# drivers_lvds.net
KiCad netlist of a schematic drawn in Altium Designer
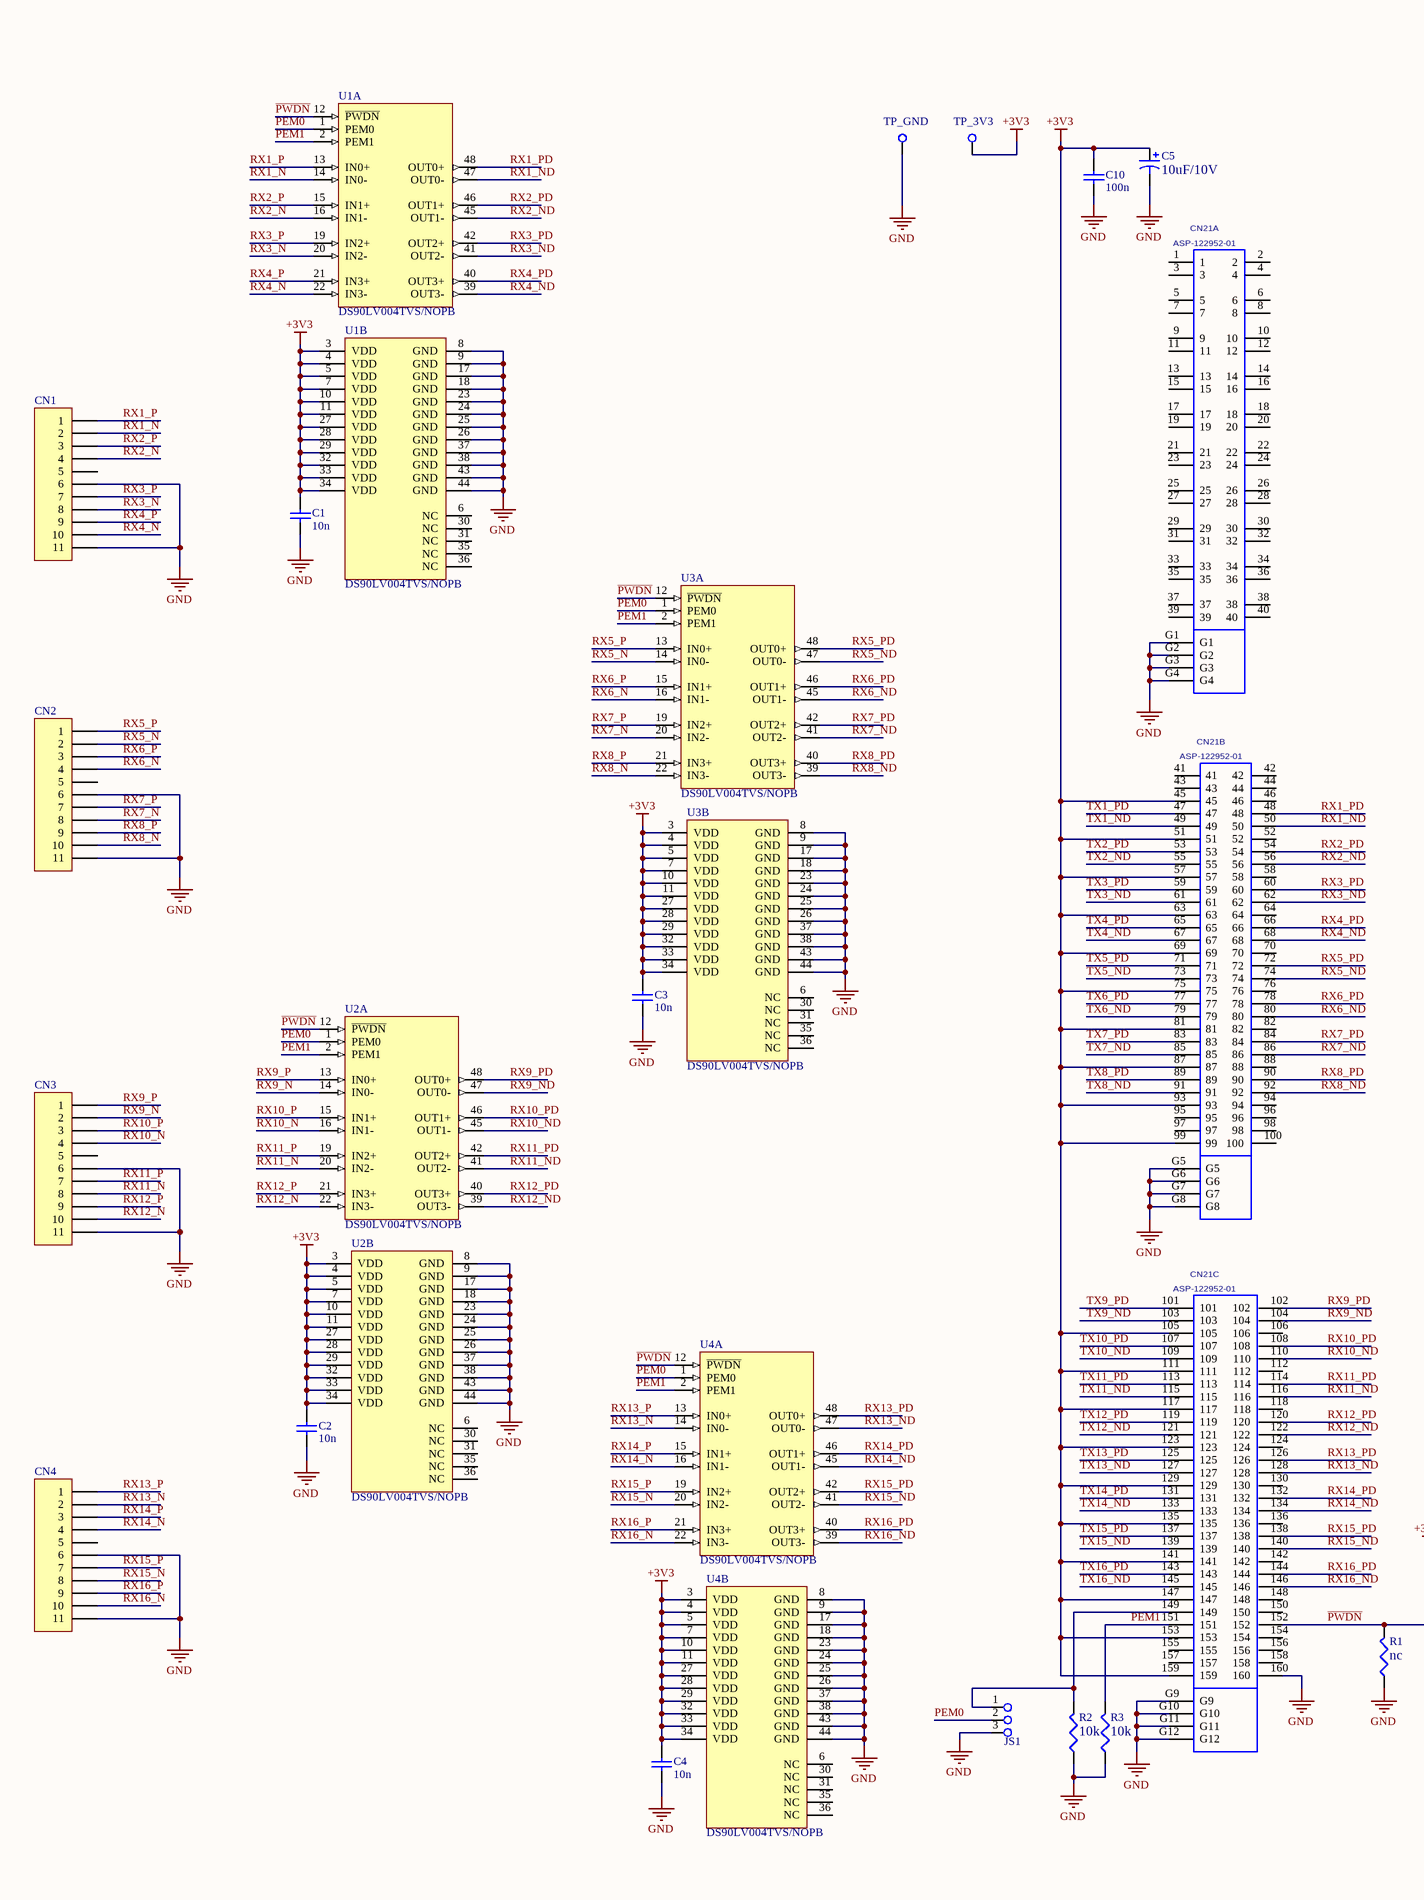
[diagram p0: drivers_lvds.SchDoc, left]
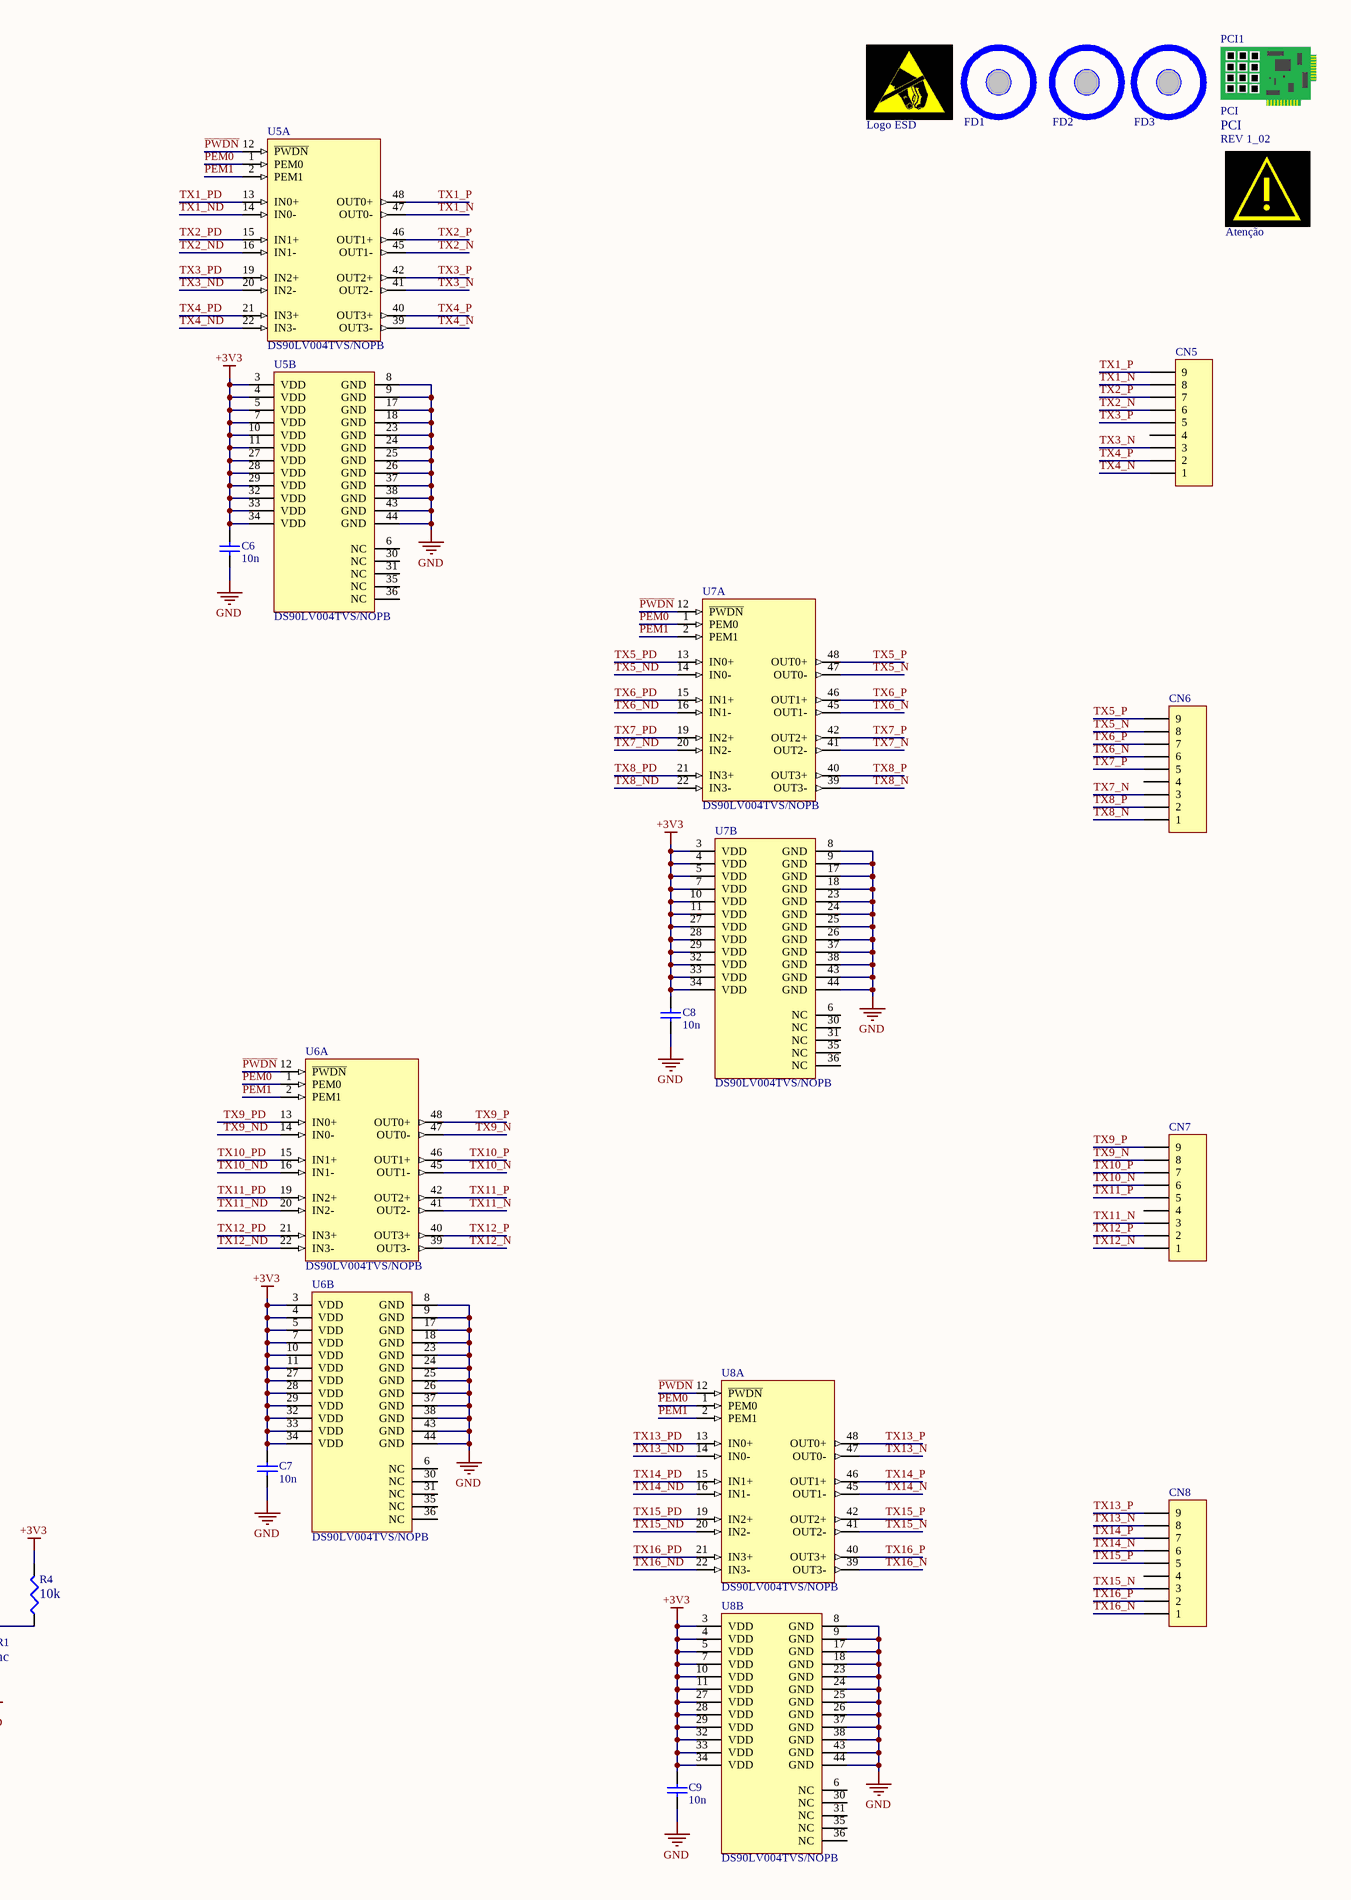
[diagram p1: drivers_lvds.SchDoc, right]

(export (version "E")
  (design (tool "Eeschema 10.0.6"))
  (components
    (comp (ref "AT3")
      (value "##nl")
      (footprint "LEIA_DOCUMENTACAO")
      (description "ATENCAO")
      (fields (field (name "VALOR") "Atenção"))
      (libsource (lib "SIMBOLOS") (part "ATENCAO"))
    )
    (comp (ref "C1")
      (value "Capacitor Cerâmico SMD")
      (footprint "0603 - CAP - montagem na maquina")
      (fields (field (name "VALOR") "10n"))
      (libsource (lib "Miscellaneous Devices") (part "Capacitor Cerâmico SMD"))
    )
    (comp (ref "C2")
      (value "Capacitor Cerâmico SMD")
      (footprint "0603 - CAP - montagem na maquina")
      (fields (field (name "VALOR") "10n"))
      (libsource (lib "Miscellaneous Devices") (part "Capacitor Cerâmico SMD"))
    )
    (comp (ref "C3")
      (value "Capacitor Cerâmico SMD")
      (footprint "0603 - CAP - montagem na maquina")
      (fields (field (name "VALOR") "10n"))
      (libsource (lib "Miscellaneous Devices") (part "Capacitor Cerâmico SMD"))
    )
    (comp (ref "C4")
      (value "Capacitor Cerâmico SMD")
      (footprint "0603 - CAP - montagem na maquina")
      (fields (field (name "VALOR") "10n"))
      (libsource (lib "Miscellaneous Devices") (part "Capacitor Cerâmico SMD"))
    )
    (comp (ref "C5")
      (value "Capacitor de tântalo")
      (footprint "CASE-B")
      (fields (field (name "VALOR") "10uF/10V"))
      (libsource (lib "Miscellaneous Devices") (part "Capacitor de tântalo"))
    )
    (comp (ref "C6")
      (value "Capacitor Cerâmico SMD")
      (footprint "0603 - CAP - montagem na maquina")
      (fields (field (name "VALOR") "10n"))
      (libsource (lib "Miscellaneous Devices") (part "Capacitor Cerâmico SMD"))
    )
    (comp (ref "C7")
      (value "Capacitor Cerâmico SMD")
      (footprint "0603 - CAP - montagem na maquina")
      (fields (field (name "VALOR") "10n"))
      (libsource (lib "Miscellaneous Devices") (part "Capacitor Cerâmico SMD"))
    )
    (comp (ref "C8")
      (value "Capacitor Cerâmico SMD")
      (footprint "0603 - CAP - montagem na maquina")
      (fields (field (name "VALOR") "10n"))
      (libsource (lib "Miscellaneous Devices") (part "Capacitor Cerâmico SMD"))
    )
    (comp (ref "C9")
      (value "Capacitor Cerâmico SMD")
      (footprint "0603 - CAP - montagem na maquina")
      (fields (field (name "VALOR") "10n"))
      (libsource (lib "Miscellaneous Devices") (part "Capacitor Cerâmico SMD"))
    )
    (comp (ref "C10")
      (value "Capacitor Cerâmico SMD")
      (footprint "0603 - CAP - montagem na maquina")
      (fields (field (name "VALOR") "100n"))
      (libsource (lib "Miscellaneous Devices") (part "Capacitor Cerâmico SMD"))
    )
    (comp (ref "CN1")
      (value "MHDR1X11")
      (footprint "MHDR1X11_Axonn")
      (description "Header, 11-Pin")
      (fields (field (name "PUBLISHER") "Altium Limited"))
      (libsource (lib "Miscellaneous Connectors") (part "MHDR1X11"))
    )
    (comp (ref "CN2")
      (value "MHDR1X11")
      (footprint "MHDR1X11_Axonn")
      (description "Header, 11-Pin")
      (fields (field (name "PUBLISHER") "Altium Limited"))
      (libsource (lib "Miscellaneous Connectors") (part "MHDR1X11"))
    )
    (comp (ref "CN3")
      (value "MHDR1X11")
      (footprint "MHDR1X11_Axonn")
      (description "Header, 11-Pin")
      (fields (field (name "PUBLISHER") "Altium Limited"))
      (libsource (lib "Miscellaneous Connectors") (part "MHDR1X11"))
    )
    (comp (ref "CN4")
      (value "MHDR1X11")
      (footprint "MHDR1X11_Axonn")
      (description "Header, 11-Pin")
      (fields (field (name "PUBLISHER") "Altium Limited"))
      (libsource (lib "Miscellaneous Connectors") (part "MHDR1X11"))
    )
    (comp (ref "CN5")
      (value "MHDR1X9")
      (footprint "MHDR1X9_Axonn")
      (description "Header, 9-Pin")
      (fields (field (name "PUBLISHER") "Altium Limited"))
      (libsource (lib "Miscellaneous Connectors") (part "MHDR1X9"))
    )
    (comp (ref "CN6")
      (value "MHDR1X9")
      (footprint "MHDR1X9_Axonn")
      (description "Header, 9-Pin")
      (fields (field (name "PUBLISHER") "Altium Limited"))
      (libsource (lib "Miscellaneous Connectors") (part "MHDR1X9"))
    )
    (comp (ref "CN7")
      (value "MHDR1X9")
      (footprint "MHDR1X9_Axonn")
      (description "Header, 9-Pin")
      (fields (field (name "PUBLISHER") "Altium Limited"))
      (libsource (lib "Miscellaneous Connectors") (part "MHDR1X9"))
    )
    (comp (ref "CN8")
      (value "MHDR1X9")
      (footprint "MHDR1X9_Axonn")
      (description "Header, 9-Pin")
      (fields (field (name "PUBLISHER") "Altium Limited"))
      (libsource (lib "Miscellaneous Connectors") (part "MHDR1X9"))
    )
    (comp (ref "CN21")
      (value "ASP-122952-01")
      (footprint "ASP-122952-01")
      (description "0.5MM PITCH DOUBLE ROW HS TERMINAL ASSEMBLY")
      (fields (field (name "MANUFACTURER") "SAMTEC") (field (name "CREATED") "May 29, 2015 - Wendy Xin"))
      (libsource (lib "ASP-122952-01") (part "ASP-122952-01"))
    )
    (comp (ref "ESD2")
      (value "##nl")
      (footprint "ESTATICA")
      (description "ESD")
      (fields (field (name "VALOR") "Logo ESD"))
      (libsource (lib "SIMBOLOS") (part "ESD"))
    )
    (comp (ref "FD1")
      (value "##nl")
      (footprint "FIDUCIAL")
      (description "Fiducial")
      (libsource (lib "PERIFERICOS") (part "Fiducial"))
    )
    (comp (ref "FD2")
      (value "##nl")
      (footprint "FIDUCIAL")
      (description "Fiducial")
      (libsource (lib "PERIFERICOS") (part "Fiducial"))
    )
    (comp (ref "FD3")
      (value "##nl")
      (footprint "FIDUCIAL")
      (description "Fiducial")
      (libsource (lib "PERIFERICOS") (part "Fiducial"))
    )
    (comp (ref "JS1")
      (value "##Obs")
      (footprint "Jumper de solda 3 vias")
      (description "JUMPER DE SOLDA 3 VIAS")
      (libsource (lib "Miscellaneous Devices") (part "JUMPER SOLDA 3 VIAS"))
    )
    (comp (ref "PCI1")
      (value "PCI")
      (fields (field (name "VALOR") "PCI") (field (name "REV") "REV 1_02"))
      (libsource (lib "PCI") (part "PCI"))
    )
    (comp (ref "R1")
      (value "Res3")
      (footprint "0603 - MONTAGEM MÁQUINA")
      (description "Resistor")
      (fields (field (name "VALOR") "nc"))
      (libsource (lib "Miscellaneous Devices") (part "Res3"))
    )
    (comp (ref "R2")
      (value "Res3")
      (footprint "0603 - MONTAGEM MÁQUINA")
      (description "Resistor")
      (fields (field (name "VALOR") "10k"))
      (libsource (lib "Miscellaneous Devices") (part "Res3"))
    )
    (comp (ref "R3")
      (value "Res3")
      (footprint "0603 - MONTAGEM MÁQUINA")
      (description "Resistor")
      (fields (field (name "VALOR") "10k"))
      (libsource (lib "Miscellaneous Devices") (part "Res3"))
    )
    (comp (ref "R4")
      (value "Res3")
      (footprint "0603 - MONTAGEM MÁQUINA")
      (description "Resistor")
      (fields (field (name "VALOR") "10k"))
      (libsource (lib "Miscellaneous Devices") (part "Res3"))
    )
    (comp (ref "TP_3V3")
      (value "Comment")
      (footprint "Testpoint")
      (description "Testpoint")
      (libsource (lib "Miscellaneous Devices") (part "TESTPOINT"))
    )
    (comp (ref "TP_GND")
      (value "Comment")
      (footprint "Testpoint")
      (description "Testpoint")
      (libsource (lib "Miscellaneous Devices") (part "TESTPOINT"))
    )
    (comp (ref "U1")
      (value "DS90LV004TVS/NOPB")
      (footprint "VBC48A_N")
      (description "4-Channel LVDS Buffer/Repeaters with Pre-Emphasis, 48-pin TQFP, Pb-Free")
      (fields
        (field (name "MANUFACTURER") "National Semiconductor")
        (field (name "PUBLISHER") "Altium Limited")
      )
      (libsource (lib "NSC Interface") (part "DS90LV004TVS/NOPB"))
    )
    (comp (ref "U2")
      (value "DS90LV004TVS/NOPB")
      (footprint "VBC48A_N")
      (description "4-Channel LVDS Buffer/Repeaters with Pre-Emphasis, 48-pin TQFP, Pb-Free")
      (fields
        (field (name "MANUFACTURER") "National Semiconductor")
        (field (name "PUBLISHER") "Altium Limited")
      )
      (libsource (lib "NSC Interface") (part "DS90LV004TVS/NOPB"))
    )
    (comp (ref "U3")
      (value "DS90LV004TVS/NOPB")
      (footprint "VBC48A_N")
      (description "4-Channel LVDS Buffer/Repeaters with Pre-Emphasis, 48-pin TQFP, Pb-Free")
      (fields
        (field (name "MANUFACTURER") "National Semiconductor")
        (field (name "PUBLISHER") "Altium Limited")
      )
      (libsource (lib "NSC Interface") (part "DS90LV004TVS/NOPB"))
    )
    (comp (ref "U4")
      (value "DS90LV004TVS/NOPB")
      (footprint "VBC48A_N")
      (description "4-Channel LVDS Buffer/Repeaters with Pre-Emphasis, 48-pin TQFP, Pb-Free")
      (fields
        (field (name "MANUFACTURER") "National Semiconductor")
        (field (name "PUBLISHER") "Altium Limited")
      )
      (libsource (lib "NSC Interface") (part "DS90LV004TVS/NOPB"))
    )
    (comp (ref "U5")
      (value "DS90LV004TVS/NOPB")
      (footprint "VBC48A_N")
      (description "4-Channel LVDS Buffer/Repeaters with Pre-Emphasis, 48-pin TQFP, Pb-Free")
      (fields
        (field (name "MANUFACTURER") "National Semiconductor")
        (field (name "PUBLISHER") "Altium Limited")
      )
      (libsource (lib "NSC Interface") (part "DS90LV004TVS/NOPB"))
    )
    (comp (ref "U6")
      (value "DS90LV004TVS/NOPB")
      (footprint "VBC48A_N")
      (description "4-Channel LVDS Buffer/Repeaters with Pre-Emphasis, 48-pin TQFP, Pb-Free")
      (fields
        (field (name "MANUFACTURER") "National Semiconductor")
        (field (name "PUBLISHER") "Altium Limited")
      )
      (libsource (lib "NSC Interface") (part "DS90LV004TVS/NOPB"))
    )
    (comp (ref "U7")
      (value "DS90LV004TVS/NOPB")
      (footprint "VBC48A_N")
      (description "4-Channel LVDS Buffer/Repeaters with Pre-Emphasis, 48-pin TQFP, Pb-Free")
      (fields
        (field (name "MANUFACTURER") "National Semiconductor")
        (field (name "PUBLISHER") "Altium Limited")
      )
      (libsource (lib "NSC Interface") (part "DS90LV004TVS/NOPB"))
    )
    (comp (ref "U8")
      (value "DS90LV004TVS/NOPB")
      (footprint "VBC48A_N")
      (description "4-Channel LVDS Buffer/Repeaters with Pre-Emphasis, 48-pin TQFP, Pb-Free")
      (fields
        (field (name "MANUFACTURER") "National Semiconductor")
        (field (name "PUBLISHER") "Altium Limited")
      )
      (libsource (lib "NSC Interface") (part "DS90LV004TVS/NOPB"))
    )
  )
  (nets
    (net (code "1") (name "+3V3") (class "Default")
      (node (ref "C1") (pin "2") (pinfunction "2_2") (pintype "passive"))
      (node (ref "C10") (pin "2") (pinfunction "2_2") (pintype "passive"))
      (node (ref "C2") (pin "2") (pinfunction "2_2") (pintype "passive"))
      (node (ref "C3") (pin "2") (pinfunction "2_2") (pintype "passive"))
      (node (ref "C4") (pin "2") (pinfunction "2_2") (pintype "passive"))
      (node (ref "C5") (pin "1") (pinfunction "1_1") (pintype "passive"))
      (node (ref "C6") (pin "2") (pinfunction "2_2") (pintype "passive"))
      (node (ref "C7") (pin "2") (pinfunction "2_2") (pintype "passive"))
      (node (ref "C8") (pin "2") (pinfunction "2_2") (pintype "passive"))
      (node (ref "C9") (pin "2") (pinfunction "2_2") (pintype "passive"))
      (node (ref "CN21") (pin "105") (pinfunction "105_105") (pintype "passive"))
      (node (ref "CN21") (pin "111") (pinfunction "111_111") (pintype "passive"))
      (node (ref "CN21") (pin "117") (pinfunction "117_117") (pintype "passive"))
      (node (ref "CN21") (pin "123") (pinfunction "123_123") (pintype "passive"))
      (node (ref "CN21") (pin "129") (pinfunction "129_129") (pintype "passive"))
      (node (ref "CN21") (pin "135") (pinfunction "135_135") (pintype "passive"))
      (node (ref "CN21") (pin "141") (pinfunction "141_141") (pintype "passive"))
      (node (ref "CN21") (pin "147") (pinfunction "147_147") (pintype "passive"))
      (node (ref "CN21") (pin "153") (pinfunction "153_153") (pintype "passive"))
      (node (ref "CN21") (pin "159") (pinfunction "159_159") (pintype "passive"))
      (node (ref "CN21") (pin "45") (pinfunction "45_45") (pintype "passive"))
      (node (ref "CN21") (pin "51") (pinfunction "51_51") (pintype "passive"))
      (node (ref "CN21") (pin "57") (pinfunction "57_57") (pintype "passive"))
      (node (ref "CN21") (pin "63") (pinfunction "63_63") (pintype "passive"))
      (node (ref "CN21") (pin "69") (pinfunction "69_69") (pintype "passive"))
      (node (ref "CN21") (pin "75") (pinfunction "75_75") (pintype "passive"))
      (node (ref "CN21") (pin "81") (pinfunction "81_81") (pintype "passive"))
      (node (ref "CN21") (pin "87") (pinfunction "87_87") (pintype "passive"))
      (node (ref "CN21") (pin "93") (pinfunction "93_93") (pintype "passive"))
      (node (ref "CN21") (pin "99") (pinfunction "99_99") (pintype "passive"))
      (node (ref "R4") (pin "2") (pinfunction "2_2") (pintype "passive"))
      (node (ref "TP_3V3") (pin "1") (pinfunction "1_1") (pintype "passive"))
      (node (ref "U1") (pin "10") (pinfunction "VDD_10") (pintype "power_in"))
      (node (ref "U1") (pin "11") (pinfunction "VDD_11") (pintype "power_in"))
      (node (ref "U1") (pin "27") (pinfunction "VDD_27") (pintype "power_in"))
      (node (ref "U1") (pin "28") (pinfunction "VDD_28") (pintype "power_in"))
      (node (ref "U1") (pin "29") (pinfunction "VDD_29") (pintype "power_in"))
      (node (ref "U1") (pin "3") (pinfunction "VDD_3") (pintype "power_in"))
      (node (ref "U1") (pin "32") (pinfunction "VDD_32") (pintype "power_in"))
      (node (ref "U1") (pin "33") (pinfunction "VDD_33") (pintype "power_in"))
      (node (ref "U1") (pin "34") (pinfunction "VDD_34") (pintype "power_in"))
      (node (ref "U1") (pin "4") (pinfunction "VDD_4") (pintype "power_in"))
      (node (ref "U1") (pin "5") (pinfunction "VDD_5") (pintype "power_in"))
      (node (ref "U1") (pin "7") (pinfunction "VDD_7") (pintype "power_in"))
      (node (ref "U2") (pin "10") (pinfunction "VDD_10") (pintype "power_in"))
      (node (ref "U2") (pin "11") (pinfunction "VDD_11") (pintype "power_in"))
      (node (ref "U2") (pin "27") (pinfunction "VDD_27") (pintype "power_in"))
      (node (ref "U2") (pin "28") (pinfunction "VDD_28") (pintype "power_in"))
      (node (ref "U2") (pin "29") (pinfunction "VDD_29") (pintype "power_in"))
      (node (ref "U2") (pin "3") (pinfunction "VDD_3") (pintype "power_in"))
      (node (ref "U2") (pin "32") (pinfunction "VDD_32") (pintype "power_in"))
      (node (ref "U2") (pin "33") (pinfunction "VDD_33") (pintype "power_in"))
      (node (ref "U2") (pin "34") (pinfunction "VDD_34") (pintype "power_in"))
      (node (ref "U2") (pin "4") (pinfunction "VDD_4") (pintype "power_in"))
      (node (ref "U2") (pin "5") (pinfunction "VDD_5") (pintype "power_in"))
      (node (ref "U2") (pin "7") (pinfunction "VDD_7") (pintype "power_in"))
      (node (ref "U3") (pin "10") (pinfunction "VDD_10") (pintype "power_in"))
      (node (ref "U3") (pin "11") (pinfunction "VDD_11") (pintype "power_in"))
      (node (ref "U3") (pin "27") (pinfunction "VDD_27") (pintype "power_in"))
      (node (ref "U3") (pin "28") (pinfunction "VDD_28") (pintype "power_in"))
      (node (ref "U3") (pin "29") (pinfunction "VDD_29") (pintype "power_in"))
      (node (ref "U3") (pin "3") (pinfunction "VDD_3") (pintype "power_in"))
      (node (ref "U3") (pin "32") (pinfunction "VDD_32") (pintype "power_in"))
      (node (ref "U3") (pin "33") (pinfunction "VDD_33") (pintype "power_in"))
      (node (ref "U3") (pin "34") (pinfunction "VDD_34") (pintype "power_in"))
      (node (ref "U3") (pin "4") (pinfunction "VDD_4") (pintype "power_in"))
      (node (ref "U3") (pin "5") (pinfunction "VDD_5") (pintype "power_in"))
      (node (ref "U3") (pin "7") (pinfunction "VDD_7") (pintype "power_in"))
      (node (ref "U4") (pin "10") (pinfunction "VDD_10") (pintype "power_in"))
      (node (ref "U4") (pin "11") (pinfunction "VDD_11") (pintype "power_in"))
      (node (ref "U4") (pin "27") (pinfunction "VDD_27") (pintype "power_in"))
      (node (ref "U4") (pin "28") (pinfunction "VDD_28") (pintype "power_in"))
      (node (ref "U4") (pin "29") (pinfunction "VDD_29") (pintype "power_in"))
      (node (ref "U4") (pin "3") (pinfunction "VDD_3") (pintype "power_in"))
      (node (ref "U4") (pin "32") (pinfunction "VDD_32") (pintype "power_in"))
      (node (ref "U4") (pin "33") (pinfunction "VDD_33") (pintype "power_in"))
      (node (ref "U4") (pin "34") (pinfunction "VDD_34") (pintype "power_in"))
      (node (ref "U4") (pin "4") (pinfunction "VDD_4") (pintype "power_in"))
      (node (ref "U4") (pin "5") (pinfunction "VDD_5") (pintype "power_in"))
      (node (ref "U4") (pin "7") (pinfunction "VDD_7") (pintype "power_in"))
      (node (ref "U5") (pin "10") (pinfunction "VDD_10") (pintype "power_in"))
      (node (ref "U5") (pin "11") (pinfunction "VDD_11") (pintype "power_in"))
      (node (ref "U5") (pin "27") (pinfunction "VDD_27") (pintype "power_in"))
      (node (ref "U5") (pin "28") (pinfunction "VDD_28") (pintype "power_in"))
      (node (ref "U5") (pin "29") (pinfunction "VDD_29") (pintype "power_in"))
      (node (ref "U5") (pin "3") (pinfunction "VDD_3") (pintype "power_in"))
      (node (ref "U5") (pin "32") (pinfunction "VDD_32") (pintype "power_in"))
      (node (ref "U5") (pin "33") (pinfunction "VDD_33") (pintype "power_in"))
      (node (ref "U5") (pin "34") (pinfunction "VDD_34") (pintype "power_in"))
      (node (ref "U5") (pin "4") (pinfunction "VDD_4") (pintype "power_in"))
      (node (ref "U5") (pin "5") (pinfunction "VDD_5") (pintype "power_in"))
      (node (ref "U5") (pin "7") (pinfunction "VDD_7") (pintype "power_in"))
      (node (ref "U6") (pin "10") (pinfunction "VDD_10") (pintype "power_in"))
      (node (ref "U6") (pin "11") (pinfunction "VDD_11") (pintype "power_in"))
      (node (ref "U6") (pin "27") (pinfunction "VDD_27") (pintype "power_in"))
      (node (ref "U6") (pin "28") (pinfunction "VDD_28") (pintype "power_in"))
      (node (ref "U6") (pin "29") (pinfunction "VDD_29") (pintype "power_in"))
      (node (ref "U6") (pin "3") (pinfunction "VDD_3") (pintype "power_in"))
      (node (ref "U6") (pin "32") (pinfunction "VDD_32") (pintype "power_in"))
      (node (ref "U6") (pin "33") (pinfunction "VDD_33") (pintype "power_in"))
      (node (ref "U6") (pin "34") (pinfunction "VDD_34") (pintype "power_in"))
      (node (ref "U6") (pin "4") (pinfunction "VDD_4") (pintype "power_in"))
      (node (ref "U6") (pin "5") (pinfunction "VDD_5") (pintype "power_in"))
      (node (ref "U6") (pin "7") (pinfunction "VDD_7") (pintype "power_in"))
      (node (ref "U7") (pin "10") (pinfunction "VDD_10") (pintype "power_in"))
      (node (ref "U7") (pin "11") (pinfunction "VDD_11") (pintype "power_in"))
      (node (ref "U7") (pin "27") (pinfunction "VDD_27") (pintype "power_in"))
      (node (ref "U7") (pin "28") (pinfunction "VDD_28") (pintype "power_in"))
      (node (ref "U7") (pin "29") (pinfunction "VDD_29") (pintype "power_in"))
      (node (ref "U7") (pin "3") (pinfunction "VDD_3") (pintype "power_in"))
      (node (ref "U7") (pin "32") (pinfunction "VDD_32") (pintype "power_in"))
      (node (ref "U7") (pin "33") (pinfunction "VDD_33") (pintype "power_in"))
      (node (ref "U7") (pin "34") (pinfunction "VDD_34") (pintype "power_in"))
      (node (ref "U7") (pin "4") (pinfunction "VDD_4") (pintype "power_in"))
      (node (ref "U7") (pin "5") (pinfunction "VDD_5") (pintype "power_in"))
      (node (ref "U7") (pin "7") (pinfunction "VDD_7") (pintype "power_in"))
      (node (ref "U8") (pin "10") (pinfunction "VDD_10") (pintype "power_in"))
      (node (ref "U8") (pin "11") (pinfunction "VDD_11") (pintype "power_in"))
      (node (ref "U8") (pin "27") (pinfunction "VDD_27") (pintype "power_in"))
      (node (ref "U8") (pin "28") (pinfunction "VDD_28") (pintype "power_in"))
      (node (ref "U8") (pin "29") (pinfunction "VDD_29") (pintype "power_in"))
      (node (ref "U8") (pin "3") (pinfunction "VDD_3") (pintype "power_in"))
      (node (ref "U8") (pin "32") (pinfunction "VDD_32") (pintype "power_in"))
      (node (ref "U8") (pin "33") (pinfunction "VDD_33") (pintype "power_in"))
      (node (ref "U8") (pin "34") (pinfunction "VDD_34") (pintype "power_in"))
      (node (ref "U8") (pin "4") (pinfunction "VDD_4") (pintype "power_in"))
      (node (ref "U8") (pin "5") (pinfunction "VDD_5") (pintype "power_in"))
      (node (ref "U8") (pin "7") (pinfunction "VDD_7") (pintype "power_in"))
    )
    (net (code "2") (name "/PEM0") (class "Default")
      (node (ref "JS1") (pin "2") (pinfunction "3_2") (pintype "passive"))
      (node (ref "U1") (pin "1") (pinfunction "PEM0_1") (pintype "input"))
      (node (ref "U2") (pin "1") (pinfunction "PEM0_1") (pintype "input"))
      (node (ref "U3") (pin "1") (pinfunction "PEM0_1") (pintype "input"))
      (node (ref "U4") (pin "1") (pinfunction "PEM0_1") (pintype "input"))
      (node (ref "U5") (pin "1") (pinfunction "PEM0_1") (pintype "input"))
      (node (ref "U6") (pin "1") (pinfunction "PEM0_1") (pintype "input"))
      (node (ref "U7") (pin "1") (pinfunction "PEM0_1") (pintype "input"))
      (node (ref "U8") (pin "1") (pinfunction "PEM0_1") (pintype "input"))
    )
    (net (code "3") (name "/PEM1") (class "Default")
      (node (ref "CN21") (pin "151") (pinfunction "151_151") (pintype "passive"))
      (node (ref "R3") (pin "2") (pinfunction "2_2") (pintype "passive"))
      (node (ref "U1") (pin "2") (pinfunction "PEM1_2") (pintype "input"))
      (node (ref "U2") (pin "2") (pinfunction "PEM1_2") (pintype "input"))
      (node (ref "U3") (pin "2") (pinfunction "PEM1_2") (pintype "input"))
      (node (ref "U4") (pin "2") (pinfunction "PEM1_2") (pintype "input"))
      (node (ref "U5") (pin "2") (pinfunction "PEM1_2") (pintype "input"))
      (node (ref "U6") (pin "2") (pinfunction "PEM1_2") (pintype "input"))
      (node (ref "U7") (pin "2") (pinfunction "PEM1_2") (pintype "input"))
      (node (ref "U8") (pin "2") (pinfunction "PEM1_2") (pintype "input"))
    )
    (net (code "4") (name "/PWDN") (class "Default")
      (node (ref "CN21") (pin "152") (pinfunction "152_152") (pintype "passive"))
      (node (ref "R1") (pin "2") (pinfunction "2_2") (pintype "passive"))
      (node (ref "R4") (pin "1") (pinfunction "1_1") (pintype "passive"))
      (node (ref "U1") (pin "12") (pinfunction "~{PWDN}_12") (pintype "input"))
      (node (ref "U2") (pin "12") (pinfunction "~{PWDN}_12") (pintype "input"))
      (node (ref "U3") (pin "12") (pinfunction "~{PWDN}_12") (pintype "input"))
      (node (ref "U4") (pin "12") (pinfunction "~{PWDN}_12") (pintype "input"))
      (node (ref "U5") (pin "12") (pinfunction "~{PWDN}_12") (pintype "input"))
      (node (ref "U6") (pin "12") (pinfunction "~{PWDN}_12") (pintype "input"))
      (node (ref "U7") (pin "12") (pinfunction "~{PWDN}_12") (pintype "input"))
      (node (ref "U8") (pin "12") (pinfunction "~{PWDN}_12") (pintype "input"))
    )
    (net (code "5") (name "/RX1_N") (class "Default")
      (node (ref "CN1") (pin "2") (pinfunction "2_2") (pintype "passive"))
      (node (ref "U1") (pin "14") (pinfunction "IN0-_14") (pintype "input"))
    )
    (net (code "6") (name "/RX1_ND") (class "Default")
      (node (ref "CN21") (pin "50") (pinfunction "50_50") (pintype "passive"))
      (node (ref "U1") (pin "47") (pinfunction "OUT0-_47") (pintype "output"))
    )
    (net (code "7") (name "/RX1_P") (class "Default")
      (node (ref "CN1") (pin "1") (pinfunction "1_1") (pintype "passive"))
      (node (ref "U1") (pin "13") (pinfunction "IN0+_13") (pintype "input"))
    )
    (net (code "8") (name "/RX1_PD") (class "Default")
      (node (ref "CN21") (pin "48") (pinfunction "48_48") (pintype "passive"))
      (node (ref "U1") (pin "48") (pinfunction "OUT0+_48") (pintype "output"))
    )
    (net (code "9") (name "/RX2_N") (class "Default")
      (node (ref "CN1") (pin "4") (pinfunction "4_4") (pintype "passive"))
      (node (ref "U1") (pin "16") (pinfunction "IN1-_16") (pintype "input"))
    )
    (net (code "10") (name "/RX2_ND") (class "Default")
      (node (ref "CN21") (pin "56") (pinfunction "56_56") (pintype "passive"))
      (node (ref "U1") (pin "45") (pinfunction "OUT1-_45") (pintype "output"))
    )
    (net (code "11") (name "/RX2_P") (class "Default")
      (node (ref "CN1") (pin "3") (pinfunction "3_3") (pintype "passive"))
      (node (ref "U1") (pin "15") (pinfunction "IN1+_15") (pintype "input"))
    )
    (net (code "12") (name "/RX2_PD") (class "Default")
      (node (ref "CN21") (pin "54") (pinfunction "54_54") (pintype "passive"))
      (node (ref "U1") (pin "46") (pinfunction "OUT1+_46") (pintype "output"))
    )
    (net (code "13") (name "/RX3_N") (class "Default")
      (node (ref "CN1") (pin "8") (pinfunction "8_8") (pintype "passive"))
      (node (ref "U1") (pin "20") (pinfunction "IN2-_20") (pintype "input"))
    )
    (net (code "14") (name "/RX3_ND") (class "Default")
      (node (ref "CN21") (pin "62") (pinfunction "62_62") (pintype "passive"))
      (node (ref "U1") (pin "41") (pinfunction "OUT2-_41") (pintype "output"))
    )
    (net (code "15") (name "/RX3_P") (class "Default")
      (node (ref "CN1") (pin "7") (pinfunction "7_7") (pintype "passive"))
      (node (ref "U1") (pin "19") (pinfunction "IN2+_19") (pintype "input"))
    )
    (net (code "16") (name "/RX3_PD") (class "Default")
      (node (ref "CN21") (pin "60") (pinfunction "60_60") (pintype "passive"))
      (node (ref "U1") (pin "42") (pinfunction "OUT2+_42") (pintype "output"))
    )
    (net (code "17") (name "/RX4_N") (class "Default")
      (node (ref "CN1") (pin "10") (pinfunction "10_10") (pintype "passive"))
      (node (ref "U1") (pin "22") (pinfunction "IN3-_22") (pintype "input"))
    )
    (net (code "18") (name "/RX4_ND") (class "Default")
      (node (ref "CN21") (pin "68") (pinfunction "68_68") (pintype "passive"))
      (node (ref "U1") (pin "39") (pinfunction "OUT3-_39") (pintype "output"))
    )
    (net (code "19") (name "/RX4_P") (class "Default")
      (node (ref "CN1") (pin "9") (pinfunction "9_9") (pintype "passive"))
      (node (ref "U1") (pin "21") (pinfunction "IN3+_21") (pintype "input"))
    )
    (net (code "20") (name "/RX4_PD") (class "Default")
      (node (ref "CN21") (pin "66") (pinfunction "66_66") (pintype "passive"))
      (node (ref "U1") (pin "40") (pinfunction "OUT3+_40") (pintype "output"))
    )
    (net (code "21") (name "/RX5_N") (class "Default")
      (node (ref "CN2") (pin "2") (pinfunction "2_2") (pintype "passive"))
      (node (ref "U3") (pin "14") (pinfunction "IN0-_14") (pintype "input"))
    )
    (net (code "22") (name "/RX5_ND") (class "Default")
      (node (ref "CN21") (pin "74") (pinfunction "74_74") (pintype "passive"))
      (node (ref "U3") (pin "47") (pinfunction "OUT0-_47") (pintype "output"))
    )
    (net (code "23") (name "/RX5_P") (class "Default")
      (node (ref "CN2") (pin "1") (pinfunction "1_1") (pintype "passive"))
      (node (ref "U3") (pin "13") (pinfunction "IN0+_13") (pintype "input"))
    )
    (net (code "24") (name "/RX5_PD") (class "Default")
      (node (ref "CN21") (pin "72") (pinfunction "72_72") (pintype "passive"))
      (node (ref "U3") (pin "48") (pinfunction "OUT0+_48") (pintype "output"))
    )
    (net (code "25") (name "/RX6_N") (class "Default")
      (node (ref "CN2") (pin "4") (pinfunction "4_4") (pintype "passive"))
      (node (ref "U3") (pin "16") (pinfunction "IN1-_16") (pintype "input"))
    )
    (net (code "26") (name "/RX6_ND") (class "Default")
      (node (ref "CN21") (pin "80") (pinfunction "80_80") (pintype "passive"))
      (node (ref "U3") (pin "45") (pinfunction "OUT1-_45") (pintype "output"))
    )
    (net (code "27") (name "/RX6_P") (class "Default")
      (node (ref "CN2") (pin "3") (pinfunction "3_3") (pintype "passive"))
      (node (ref "U3") (pin "15") (pinfunction "IN1+_15") (pintype "input"))
    )
    (net (code "28") (name "/RX6_PD") (class "Default")
      (node (ref "CN21") (pin "78") (pinfunction "78_78") (pintype "passive"))
      (node (ref "U3") (pin "46") (pinfunction "OUT1+_46") (pintype "output"))
    )
    (net (code "29") (name "/RX7_N") (class "Default")
      (node (ref "CN2") (pin "8") (pinfunction "8_8") (pintype "passive"))
      (node (ref "U3") (pin "20") (pinfunction "IN2-_20") (pintype "input"))
    )
    (net (code "30") (name "/RX7_ND") (class "Default")
      (node (ref "CN21") (pin "86") (pinfunction "86_86") (pintype "passive"))
      (node (ref "U3") (pin "41") (pinfunction "OUT2-_41") (pintype "output"))
    )
    (net (code "31") (name "/RX7_P") (class "Default")
      (node (ref "CN2") (pin "7") (pinfunction "7_7") (pintype "passive"))
      (node (ref "U3") (pin "19") (pinfunction "IN2+_19") (pintype "input"))
    )
    (net (code "32") (name "/RX7_PD") (class "Default")
      (node (ref "CN21") (pin "84") (pinfunction "84_84") (pintype "passive"))
      (node (ref "U3") (pin "42") (pinfunction "OUT2+_42") (pintype "output"))
    )
    (net (code "33") (name "/RX8_N") (class "Default")
      (node (ref "CN2") (pin "10") (pinfunction "10_10") (pintype "passive"))
      (node (ref "U3") (pin "22") (pinfunction "IN3-_22") (pintype "input"))
    )
    (net (code "34") (name "/RX8_ND") (class "Default")
      (node (ref "CN21") (pin "92") (pinfunction "92_92") (pintype "passive"))
      (node (ref "U3") (pin "39") (pinfunction "OUT3-_39") (pintype "output"))
    )
    (net (code "35") (name "/RX8_P") (class "Default")
      (node (ref "CN2") (pin "9") (pinfunction "9_9") (pintype "passive"))
      (node (ref "U3") (pin "21") (pinfunction "IN3+_21") (pintype "input"))
    )
    (net (code "36") (name "/RX8_PD") (class "Default")
      (node (ref "CN21") (pin "90") (pinfunction "90_90") (pintype "passive"))
      (node (ref "U3") (pin "40") (pinfunction "OUT3+_40") (pintype "output"))
    )
    (net (code "37") (name "/RX9_N") (class "Default")
      (node (ref "CN3") (pin "2") (pinfunction "2_2") (pintype "passive"))
      (node (ref "U2") (pin "14") (pinfunction "IN0-_14") (pintype "input"))
    )
    (net (code "38") (name "/RX9_ND") (class "Default")
      (node (ref "CN21") (pin "104") (pinfunction "104_104") (pintype "passive"))
      (node (ref "U2") (pin "47") (pinfunction "OUT0-_47") (pintype "output"))
    )
    (net (code "39") (name "/RX9_P") (class "Default")
      (node (ref "CN3") (pin "1") (pinfunction "1_1") (pintype "passive"))
      (node (ref "U2") (pin "13") (pinfunction "IN0+_13") (pintype "input"))
    )
    (net (code "40") (name "/RX9_PD") (class "Default")
      (node (ref "CN21") (pin "102") (pinfunction "102_102") (pintype "passive"))
      (node (ref "U2") (pin "48") (pinfunction "OUT0+_48") (pintype "output"))
    )
    (net (code "41") (name "/RX10_N") (class "Default")
      (node (ref "CN3") (pin "4") (pinfunction "4_4") (pintype "passive"))
      (node (ref "U2") (pin "16") (pinfunction "IN1-_16") (pintype "input"))
    )
    (net (code "42") (name "/RX10_ND") (class "Default")
      (node (ref "CN21") (pin "110") (pinfunction "110_110") (pintype "passive"))
      (node (ref "U2") (pin "45") (pinfunction "OUT1-_45") (pintype "output"))
    )
    (net (code "43") (name "/RX10_P") (class "Default")
      (node (ref "CN3") (pin "3") (pinfunction "3_3") (pintype "passive"))
      (node (ref "U2") (pin "15") (pinfunction "IN1+_15") (pintype "input"))
    )
    (net (code "44") (name "/RX10_PD") (class "Default")
      (node (ref "CN21") (pin "108") (pinfunction "108_108") (pintype "passive"))
      (node (ref "U2") (pin "46") (pinfunction "OUT1+_46") (pintype "output"))
    )
    (net (code "45") (name "/RX11_N") (class "Default")
      (node (ref "CN3") (pin "8") (pinfunction "8_8") (pintype "passive"))
      (node (ref "U2") (pin "20") (pinfunction "IN2-_20") (pintype "input"))
    )
    (net (code "46") (name "/RX11_ND") (class "Default")
      (node (ref "CN21") (pin "116") (pinfunction "116_116") (pintype "passive"))
      (node (ref "U2") (pin "41") (pinfunction "OUT2-_41") (pintype "output"))
    )
    (net (code "47") (name "/RX11_P") (class "Default")
      (node (ref "CN3") (pin "7") (pinfunction "7_7") (pintype "passive"))
      (node (ref "U2") (pin "19") (pinfunction "IN2+_19") (pintype "input"))
    )
    (net (code "48") (name "/RX11_PD") (class "Default")
      (node (ref "CN21") (pin "114") (pinfunction "114_114") (pintype "passive"))
      (node (ref "U2") (pin "42") (pinfunction "OUT2+_42") (pintype "output"))
    )
    (net (code "49") (name "/RX12_N") (class "Default")
      (node (ref "CN3") (pin "10") (pinfunction "10_10") (pintype "passive"))
      (node (ref "U2") (pin "22") (pinfunction "IN3-_22") (pintype "input"))
    )
    (net (code "50") (name "/RX12_ND") (class "Default")
      (node (ref "CN21") (pin "122") (pinfunction "122_122") (pintype "passive"))
      (node (ref "U2") (pin "39") (pinfunction "OUT3-_39") (pintype "output"))
    )
    (net (code "51") (name "/RX12_P") (class "Default")
      (node (ref "CN3") (pin "9") (pinfunction "9_9") (pintype "passive"))
      (node (ref "U2") (pin "21") (pinfunction "IN3+_21") (pintype "input"))
    )
    (net (code "52") (name "/RX12_PD") (class "Default")
      (node (ref "CN21") (pin "120") (pinfunction "120_120") (pintype "passive"))
      (node (ref "U2") (pin "40") (pinfunction "OUT3+_40") (pintype "output"))
    )
    (net (code "53") (name "/RX13_N") (class "Default")
      (node (ref "CN4") (pin "2") (pinfunction "2_2") (pintype "passive"))
      (node (ref "U4") (pin "14") (pinfunction "IN0-_14") (pintype "input"))
    )
    (net (code "54") (name "/RX13_ND") (class "Default")
      (node (ref "CN21") (pin "128") (pinfunction "128_128") (pintype "passive"))
      (node (ref "U4") (pin "47") (pinfunction "OUT0-_47") (pintype "output"))
    )
    (net (code "55") (name "/RX13_P") (class "Default")
      (node (ref "CN4") (pin "1") (pinfunction "1_1") (pintype "passive"))
      (node (ref "U4") (pin "13") (pinfunction "IN0+_13") (pintype "input"))
    )
    (net (code "56") (name "/RX13_PD") (class "Default")
      (node (ref "CN21") (pin "126") (pinfunction "126_126") (pintype "passive"))
      (node (ref "U4") (pin "48") (pinfunction "OUT0+_48") (pintype "output"))
    )
    (net (code "57") (name "/RX14_N") (class "Default")
      (node (ref "CN4") (pin "4") (pinfunction "4_4") (pintype "passive"))
      (node (ref "U4") (pin "16") (pinfunction "IN1-_16") (pintype "input"))
    )
    (net (code "58") (name "/RX14_ND") (class "Default")
      (node (ref "CN21") (pin "134") (pinfunction "134_134") (pintype "passive"))
      (node (ref "U4") (pin "45") (pinfunction "OUT1-_45") (pintype "output"))
    )
    (net (code "59") (name "/RX14_P") (class "Default")
      (node (ref "CN4") (pin "3") (pinfunction "3_3") (pintype "passive"))
      (node (ref "U4") (pin "15") (pinfunction "IN1+_15") (pintype "input"))
    )
    (net (code "60") (name "/RX14_PD") (class "Default")
      (node (ref "CN21") (pin "132") (pinfunction "132_132") (pintype "passive"))
      (node (ref "U4") (pin "46") (pinfunction "OUT1+_46") (pintype "output"))
    )
    (net (code "61") (name "/RX15_N") (class "Default")
      (node (ref "CN4") (pin "8") (pinfunction "8_8") (pintype "passive"))
      (node (ref "U4") (pin "20") (pinfunction "IN2-_20") (pintype "input"))
    )
    (net (code "62") (name "/RX15_ND") (class "Default")
      (node (ref "CN21") (pin "140") (pinfunction "140_140") (pintype "passive"))
      (node (ref "U4") (pin "41") (pinfunction "OUT2-_41") (pintype "output"))
    )
    (net (code "63") (name "/RX15_P") (class "Default")
      (node (ref "CN4") (pin "7") (pinfunction "7_7") (pintype "passive"))
      (node (ref "U4") (pin "19") (pinfunction "IN2+_19") (pintype "input"))
    )
    (net (code "64") (name "/RX15_PD") (class "Default")
      (node (ref "CN21") (pin "138") (pinfunction "138_138") (pintype "passive"))
      (node (ref "U4") (pin "42") (pinfunction "OUT2+_42") (pintype "output"))
    )
    (net (code "65") (name "/RX16_N") (class "Default")
      (node (ref "CN4") (pin "10") (pinfunction "10_10") (pintype "passive"))
      (node (ref "U4") (pin "22") (pinfunction "IN3-_22") (pintype "input"))
    )
    (net (code "66") (name "/RX16_ND") (class "Default")
      (node (ref "CN21") (pin "146") (pinfunction "146_146") (pintype "passive"))
      (node (ref "U4") (pin "39") (pinfunction "OUT3-_39") (pintype "output"))
    )
    (net (code "67") (name "/RX16_P") (class "Default")
      (node (ref "CN4") (pin "9") (pinfunction "9_9") (pintype "passive"))
      (node (ref "U4") (pin "21") (pinfunction "IN3+_21") (pintype "input"))
    )
    (net (code "68") (name "/RX16_PD") (class "Default")
      (node (ref "CN21") (pin "144") (pinfunction "144_144") (pintype "passive"))
      (node (ref "U4") (pin "40") (pinfunction "OUT3+_40") (pintype "output"))
    )
    (net (code "69") (name "/TX1_N") (class "Default")
      (node (ref "CN5") (pin "8") (pinfunction "8_8") (pintype "passive"))
      (node (ref "U5") (pin "47") (pinfunction "OUT0-_47") (pintype "output"))
    )
    (net (code "70") (name "/TX1_ND") (class "Default")
      (node (ref "CN21") (pin "49") (pinfunction "49_49") (pintype "passive"))
      (node (ref "U5") (pin "14") (pinfunction "IN0-_14") (pintype "input"))
    )
    (net (code "71") (name "/TX1_P") (class "Default")
      (node (ref "CN5") (pin "9") (pinfunction "9_9") (pintype "passive"))
      (node (ref "U5") (pin "48") (pinfunction "OUT0+_48") (pintype "output"))
    )
    (net (code "72") (name "/TX1_PD") (class "Default")
      (node (ref "CN21") (pin "47") (pinfunction "47_47") (pintype "passive"))
      (node (ref "U5") (pin "13") (pinfunction "IN0+_13") (pintype "input"))
    )
    (net (code "73") (name "/TX2_N") (class "Default")
      (node (ref "CN5") (pin "6") (pinfunction "6_6") (pintype "passive"))
      (node (ref "U5") (pin "45") (pinfunction "OUT1-_45") (pintype "output"))
    )
    (net (code "74") (name "/TX2_ND") (class "Default")
      (node (ref "CN21") (pin "55") (pinfunction "55_55") (pintype "passive"))
      (node (ref "U5") (pin "16") (pinfunction "IN1-_16") (pintype "input"))
    )
    (net (code "75") (name "/TX2_P") (class "Default")
      (node (ref "CN5") (pin "7") (pinfunction "7_7") (pintype "passive"))
      (node (ref "U5") (pin "46") (pinfunction "OUT1+_46") (pintype "output"))
    )
    (net (code "76") (name "/TX2_PD") (class "Default")
      (node (ref "CN21") (pin "53") (pinfunction "53_53") (pintype "passive"))
      (node (ref "U5") (pin "15") (pinfunction "IN1+_15") (pintype "input"))
    )
    (net (code "77") (name "/TX3_N") (class "Default")
      (node (ref "CN5") (pin "3") (pinfunction "3_3") (pintype "passive"))
      (node (ref "U5") (pin "41") (pinfunction "OUT2-_41") (pintype "output"))
    )
    (net (code "78") (name "/TX3_ND") (class "Default")
      (node (ref "CN21") (pin "61") (pinfunction "61_61") (pintype "passive"))
      (node (ref "U5") (pin "20") (pinfunction "IN2-_20") (pintype "input"))
    )
    (net (code "79") (name "/TX3_P") (class "Default")
      (node (ref "CN5") (pin "5") (pinfunction "5_5") (pintype "passive"))
      (node (ref "U5") (pin "42") (pinfunction "OUT2+_42") (pintype "output"))
    )
    (net (code "80") (name "/TX3_PD") (class "Default")
      (node (ref "CN21") (pin "59") (pinfunction "59_59") (pintype "passive"))
      (node (ref "U5") (pin "19") (pinfunction "IN2+_19") (pintype "input"))
    )
    (net (code "81") (name "/TX4_N") (class "Default")
      (node (ref "CN5") (pin "1") (pinfunction "1_1") (pintype "passive"))
      (node (ref "U5") (pin "39") (pinfunction "OUT3-_39") (pintype "output"))
    )
    (net (code "82") (name "/TX4_ND") (class "Default")
      (node (ref "CN21") (pin "67") (pinfunction "67_67") (pintype "passive"))
      (node (ref "U5") (pin "22") (pinfunction "IN3-_22") (pintype "input"))
    )
    (net (code "83") (name "/TX4_P") (class "Default")
      (node (ref "CN5") (pin "2") (pinfunction "2_2") (pintype "passive"))
      (node (ref "U5") (pin "40") (pinfunction "OUT3+_40") (pintype "output"))
    )
    (net (code "84") (name "/TX4_PD") (class "Default")
      (node (ref "CN21") (pin "65") (pinfunction "65_65") (pintype "passive"))
      (node (ref "U5") (pin "21") (pinfunction "IN3+_21") (pintype "input"))
    )
    (net (code "85") (name "/TX5_N") (class "Default")
      (node (ref "CN6") (pin "8") (pinfunction "8_8") (pintype "passive"))
      (node (ref "U7") (pin "47") (pinfunction "OUT0-_47") (pintype "output"))
    )
    (net (code "86") (name "/TX5_ND") (class "Default")
      (node (ref "CN21") (pin "73") (pinfunction "73_73") (pintype "passive"))
      (node (ref "U7") (pin "14") (pinfunction "IN0-_14") (pintype "input"))
    )
    (net (code "87") (name "/TX5_P") (class "Default")
      (node (ref "CN6") (pin "9") (pinfunction "9_9") (pintype "passive"))
      (node (ref "U7") (pin "48") (pinfunction "OUT0+_48") (pintype "output"))
    )
    (net (code "88") (name "/TX5_PD") (class "Default")
      (node (ref "CN21") (pin "71") (pinfunction "71_71") (pintype "passive"))
      (node (ref "U7") (pin "13") (pinfunction "IN0+_13") (pintype "input"))
    )
    (net (code "89") (name "/TX6_N") (class "Default")
      (node (ref "CN6") (pin "6") (pinfunction "6_6") (pintype "passive"))
      (node (ref "U7") (pin "45") (pinfunction "OUT1-_45") (pintype "output"))
    )
    (net (code "90") (name "/TX6_ND") (class "Default")
      (node (ref "CN21") (pin "79") (pinfunction "79_79") (pintype "passive"))
      (node (ref "U7") (pin "16") (pinfunction "IN1-_16") (pintype "input"))
    )
    (net (code "91") (name "/TX6_P") (class "Default")
      (node (ref "CN6") (pin "7") (pinfunction "7_7") (pintype "passive"))
      (node (ref "U7") (pin "46") (pinfunction "OUT1+_46") (pintype "output"))
    )
    (net (code "92") (name "/TX6_PD") (class "Default")
      (node (ref "CN21") (pin "77") (pinfunction "77_77") (pintype "passive"))
      (node (ref "U7") (pin "15") (pinfunction "IN1+_15") (pintype "input"))
    )
    (net (code "93") (name "/TX7_N") (class "Default")
      (node (ref "CN6") (pin "3") (pinfunction "3_3") (pintype "passive"))
      (node (ref "U7") (pin "41") (pinfunction "OUT2-_41") (pintype "output"))
    )
    (net (code "94") (name "/TX7_ND") (class "Default")
      (node (ref "CN21") (pin "85") (pinfunction "85_85") (pintype "passive"))
      (node (ref "U7") (pin "20") (pinfunction "IN2-_20") (pintype "input"))
    )
    (net (code "95") (name "/TX7_P") (class "Default")
      (node (ref "CN6") (pin "5") (pinfunction "5_5") (pintype "passive"))
      (node (ref "U7") (pin "42") (pinfunction "OUT2+_42") (pintype "output"))
    )
    (net (code "96") (name "/TX7_PD") (class "Default")
      (node (ref "CN21") (pin "83") (pinfunction "83_83") (pintype "passive"))
      (node (ref "U7") (pin "19") (pinfunction "IN2+_19") (pintype "input"))
    )
    (net (code "97") (name "/TX8_N") (class "Default")
      (node (ref "CN6") (pin "1") (pinfunction "1_1") (pintype "passive"))
      (node (ref "U7") (pin "39") (pinfunction "OUT3-_39") (pintype "output"))
    )
    (net (code "98") (name "/TX8_ND") (class "Default")
      (node (ref "CN21") (pin "91") (pinfunction "91_91") (pintype "passive"))
      (node (ref "U7") (pin "22") (pinfunction "IN3-_22") (pintype "input"))
    )
    (net (code "99") (name "/TX8_P") (class "Default")
      (node (ref "CN6") (pin "2") (pinfunction "2_2") (pintype "passive"))
      (node (ref "U7") (pin "40") (pinfunction "OUT3+_40") (pintype "output"))
    )
    (net (code "100") (name "/TX8_PD") (class "Default")
      (node (ref "CN21") (pin "89") (pinfunction "89_89") (pintype "passive"))
      (node (ref "U7") (pin "21") (pinfunction "IN3+_21") (pintype "input"))
    )
    (net (code "101") (name "/TX9_N") (class "Default")
      (node (ref "CN7") (pin "8") (pinfunction "8_8") (pintype "passive"))
      (node (ref "U6") (pin "47") (pinfunction "OUT0-_47") (pintype "output"))
    )
    (net (code "102") (name "/TX9_ND") (class "Default")
      (node (ref "CN21") (pin "103") (pinfunction "103_103") (pintype "passive"))
      (node (ref "U6") (pin "14") (pinfunction "IN0-_14") (pintype "input"))
    )
    (net (code "103") (name "/TX9_P") (class "Default")
      (node (ref "CN7") (pin "9") (pinfunction "9_9") (pintype "passive"))
      (node (ref "U6") (pin "48") (pinfunction "OUT0+_48") (pintype "output"))
    )
    (net (code "104") (name "/TX9_PD") (class "Default")
      (node (ref "CN21") (pin "101") (pinfunction "101_101") (pintype "passive"))
      (node (ref "U6") (pin "13") (pinfunction "IN0+_13") (pintype "input"))
    )
    (net (code "105") (name "/TX10_N") (class "Default")
      (node (ref "CN7") (pin "6") (pinfunction "6_6") (pintype "passive"))
      (node (ref "U6") (pin "45") (pinfunction "OUT1-_45") (pintype "output"))
    )
    (net (code "106") (name "/TX10_ND") (class "Default")
      (node (ref "CN21") (pin "109") (pinfunction "109_109") (pintype "passive"))
      (node (ref "U6") (pin "16") (pinfunction "IN1-_16") (pintype "input"))
    )
    (net (code "107") (name "/TX10_P") (class "Default")
      (node (ref "CN7") (pin "7") (pinfunction "7_7") (pintype "passive"))
      (node (ref "U6") (pin "46") (pinfunction "OUT1+_46") (pintype "output"))
    )
    (net (code "108") (name "/TX10_PD") (class "Default")
      (node (ref "CN21") (pin "107") (pinfunction "107_107") (pintype "passive"))
      (node (ref "U6") (pin "15") (pinfunction "IN1+_15") (pintype "input"))
    )
    (net (code "109") (name "/TX11_N") (class "Default")
      (node (ref "CN7") (pin "3") (pinfunction "3_3") (pintype "passive"))
      (node (ref "U6") (pin "41") (pinfunction "OUT2-_41") (pintype "output"))
    )
    (net (code "110") (name "/TX11_ND") (class "Default")
      (node (ref "CN21") (pin "115") (pinfunction "115_115") (pintype "passive"))
      (node (ref "U6") (pin "20") (pinfunction "IN2-_20") (pintype "input"))
    )
    (net (code "111") (name "/TX11_P") (class "Default")
      (node (ref "CN7") (pin "5") (pinfunction "5_5") (pintype "passive"))
      (node (ref "U6") (pin "42") (pinfunction "OUT2+_42") (pintype "output"))
    )
    (net (code "112") (name "/TX11_PD") (class "Default")
      (node (ref "CN21") (pin "113") (pinfunction "113_113") (pintype "passive"))
      (node (ref "U6") (pin "19") (pinfunction "IN2+_19") (pintype "input"))
    )
    (net (code "113") (name "/TX12_N") (class "Default")
      (node (ref "CN7") (pin "1") (pinfunction "1_1") (pintype "passive"))
      (node (ref "U6") (pin "39") (pinfunction "OUT3-_39") (pintype "output"))
    )
    (net (code "114") (name "/TX12_ND") (class "Default")
      (node (ref "CN21") (pin "121") (pinfunction "121_121") (pintype "passive"))
      (node (ref "U6") (pin "22") (pinfunction "IN3-_22") (pintype "input"))
    )
    (net (code "115") (name "/TX12_P") (class "Default")
      (node (ref "CN7") (pin "2") (pinfunction "2_2") (pintype "passive"))
      (node (ref "U6") (pin "40") (pinfunction "OUT3+_40") (pintype "output"))
    )
    (net (code "116") (name "/TX12_PD") (class "Default")
      (node (ref "CN21") (pin "119") (pinfunction "119_119") (pintype "passive"))
      (node (ref "U6") (pin "21") (pinfunction "IN3+_21") (pintype "input"))
    )
    (net (code "117") (name "/TX13_N") (class "Default")
      (node (ref "CN8") (pin "8") (pinfunction "8_8") (pintype "passive"))
      (node (ref "U8") (pin "47") (pinfunction "OUT0-_47") (pintype "output"))
    )
    (net (code "118") (name "/TX13_ND") (class "Default")
      (node (ref "CN21") (pin "127") (pinfunction "127_127") (pintype "passive"))
      (node (ref "U8") (pin "14") (pinfunction "IN0-_14") (pintype "input"))
    )
    (net (code "119") (name "/TX13_P") (class "Default")
      (node (ref "CN8") (pin "9") (pinfunction "9_9") (pintype "passive"))
      (node (ref "U8") (pin "48") (pinfunction "OUT0+_48") (pintype "output"))
    )
    (net (code "120") (name "/TX13_PD") (class "Default")
      (node (ref "CN21") (pin "125") (pinfunction "125_125") (pintype "passive"))
      (node (ref "U8") (pin "13") (pinfunction "IN0+_13") (pintype "input"))
    )
    (net (code "121") (name "/TX14_N") (class "Default")
      (node (ref "CN8") (pin "6") (pinfunction "6_6") (pintype "passive"))
      (node (ref "U8") (pin "45") (pinfunction "OUT1-_45") (pintype "output"))
    )
    (net (code "122") (name "/TX14_ND") (class "Default")
      (node (ref "CN21") (pin "133") (pinfunction "133_133") (pintype "passive"))
      (node (ref "U8") (pin "16") (pinfunction "IN1-_16") (pintype "input"))
    )
    (net (code "123") (name "/TX14_P") (class "Default")
      (node (ref "CN8") (pin "7") (pinfunction "7_7") (pintype "passive"))
      (node (ref "U8") (pin "46") (pinfunction "OUT1+_46") (pintype "output"))
    )
    (net (code "124") (name "/TX14_PD") (class "Default")
      (node (ref "CN21") (pin "131") (pinfunction "131_131") (pintype "passive"))
      (node (ref "U8") (pin "15") (pinfunction "IN1+_15") (pintype "input"))
    )
    (net (code "125") (name "/TX15_N") (class "Default")
      (node (ref "CN8") (pin "3") (pinfunction "3_3") (pintype "passive"))
      (node (ref "U8") (pin "41") (pinfunction "OUT2-_41") (pintype "output"))
    )
    (net (code "126") (name "/TX15_ND") (class "Default")
      (node (ref "CN21") (pin "139") (pinfunction "139_139") (pintype "passive"))
      (node (ref "U8") (pin "20") (pinfunction "IN2-_20") (pintype "input"))
    )
    (net (code "127") (name "/TX15_P") (class "Default")
      (node (ref "CN8") (pin "5") (pinfunction "5_5") (pintype "passive"))
      (node (ref "U8") (pin "42") (pinfunction "OUT2+_42") (pintype "output"))
    )
    (net (code "128") (name "/TX15_PD") (class "Default")
      (node (ref "CN21") (pin "137") (pinfunction "137_137") (pintype "passive"))
      (node (ref "U8") (pin "19") (pinfunction "IN2+_19") (pintype "input"))
    )
    (net (code "129") (name "/TX16_N") (class "Default")
      (node (ref "CN8") (pin "1") (pinfunction "1_1") (pintype "passive"))
      (node (ref "U8") (pin "39") (pinfunction "OUT3-_39") (pintype "output"))
    )
    (net (code "130") (name "/TX16_ND") (class "Default")
      (node (ref "CN21") (pin "145") (pinfunction "145_145") (pintype "passive"))
      (node (ref "U8") (pin "22") (pinfunction "IN3-_22") (pintype "input"))
    )
    (net (code "131") (name "/TX16_P") (class "Default")
      (node (ref "CN8") (pin "2") (pinfunction "2_2") (pintype "passive"))
      (node (ref "U8") (pin "40") (pinfunction "OUT3+_40") (pintype "output"))
    )
    (net (code "132") (name "/TX16_PD") (class "Default")
      (node (ref "CN21") (pin "143") (pinfunction "143_143") (pintype "passive"))
      (node (ref "U8") (pin "21") (pinfunction "IN3+_21") (pintype "input"))
    )
    (net (code "133") (name "GND") (class "Default")
      (node (ref "C1") (pin "1") (pinfunction "1_1") (pintype "passive"))
      (node (ref "C10") (pin "1") (pinfunction "1_1") (pintype "passive"))
      (node (ref "C2") (pin "1") (pinfunction "1_1") (pintype "passive"))
      (node (ref "C3") (pin "1") (pinfunction "1_1") (pintype "passive"))
      (node (ref "C4") (pin "1") (pinfunction "1_1") (pintype "passive"))
      (node (ref "C5") (pin "2") (pinfunction "2_2") (pintype "passive"))
      (node (ref "C6") (pin "1") (pinfunction "1_1") (pintype "passive"))
      (node (ref "C7") (pin "1") (pinfunction "1_1") (pintype "passive"))
      (node (ref "C8") (pin "1") (pinfunction "1_1") (pintype "passive"))
      (node (ref "C9") (pin "1") (pinfunction "1_1") (pintype "passive"))
      (node (ref "CN1") (pin "11") (pinfunction "11_11") (pintype "passive"))
      (node (ref "CN1") (pin "6") (pinfunction "6_6") (pintype "passive"))
      (node (ref "CN2") (pin "11") (pinfunction "11_11") (pintype "passive"))
      (node (ref "CN2") (pin "6") (pinfunction "6_6") (pintype "passive"))
      (node (ref "CN21") (pin "160") (pinfunction "160_160") (pintype "passive"))
      (node (ref "CN21") (pin "G1") (pinfunction "G1_G1") (pintype "passive"))
      (node (ref "CN21") (pin "G10") (pinfunction "G10_G10") (pintype "passive"))
      (node (ref "CN21") (pin "G11") (pinfunction "G11_G11") (pintype "passive"))
      (node (ref "CN21") (pin "G12") (pinfunction "G12_G12") (pintype "passive"))
      (node (ref "CN21") (pin "G2") (pinfunction "G2_G2") (pintype "passive"))
      (node (ref "CN21") (pin "G3") (pinfunction "G3_G3") (pintype "passive"))
      (node (ref "CN21") (pin "G4") (pinfunction "G4_G4") (pintype "passive"))
      (node (ref "CN21") (pin "G5") (pinfunction "G5_G5") (pintype "passive"))
      (node (ref "CN21") (pin "G6") (pinfunction "G6_G6") (pintype "passive"))
      (node (ref "CN21") (pin "G7") (pinfunction "G7_G7") (pintype "passive"))
      (node (ref "CN21") (pin "G8") (pinfunction "G8_G8") (pintype "passive"))
      (node (ref "CN21") (pin "G9") (pinfunction "G9_G9") (pintype "passive"))
      (node (ref "CN3") (pin "11") (pinfunction "11_11") (pintype "passive"))
      (node (ref "CN3") (pin "6") (pinfunction "6_6") (pintype "passive"))
      (node (ref "CN4") (pin "11") (pinfunction "11_11") (pintype "passive"))
      (node (ref "CN4") (pin "6") (pinfunction "6_6") (pintype "passive"))
      (node (ref "JS1") (pin "3") (pinfunction "5_3") (pintype "passive"))
      (node (ref "R1") (pin "1") (pinfunction "1_1") (pintype "passive"))
      (node (ref "R2") (pin "1") (pinfunction "1_1") (pintype "passive"))
      (node (ref "R3") (pin "1") (pinfunction "1_1") (pintype "passive"))
      (node (ref "TP_GND") (pin "1") (pinfunction "1_1") (pintype "passive"))
      (node (ref "U1") (pin "17") (pinfunction "GND_17") (pintype "power_in"))
      (node (ref "U1") (pin "18") (pinfunction "GND_18") (pintype "power_in"))
      (node (ref "U1") (pin "23") (pinfunction "GND_23") (pintype "power_in"))
      (node (ref "U1") (pin "24") (pinfunction "GND_24") (pintype "power_in"))
      (node (ref "U1") (pin "25") (pinfunction "GND_25") (pintype "power_in"))
      (node (ref "U1") (pin "26") (pinfunction "GND_26") (pintype "power_in"))
      (node (ref "U1") (pin "37") (pinfunction "GND_37") (pintype "power_in"))
      (node (ref "U1") (pin "38") (pinfunction "GND_38") (pintype "power_in"))
      (node (ref "U1") (pin "43") (pinfunction "GND_43") (pintype "power_in"))
      (node (ref "U1") (pin "44") (pinfunction "GND_44") (pintype "power_in"))
      (node (ref "U1") (pin "8") (pinfunction "GND_8") (pintype "power_in"))
      (node (ref "U1") (pin "9") (pinfunction "GND_9") (pintype "power_in"))
      (node (ref "U2") (pin "17") (pinfunction "GND_17") (pintype "power_in"))
      (node (ref "U2") (pin "18") (pinfunction "GND_18") (pintype "power_in"))
      (node (ref "U2") (pin "23") (pinfunction "GND_23") (pintype "power_in"))
      (node (ref "U2") (pin "24") (pinfunction "GND_24") (pintype "power_in"))
      (node (ref "U2") (pin "25") (pinfunction "GND_25") (pintype "power_in"))
      (node (ref "U2") (pin "26") (pinfunction "GND_26") (pintype "power_in"))
      (node (ref "U2") (pin "37") (pinfunction "GND_37") (pintype "power_in"))
      (node (ref "U2") (pin "38") (pinfunction "GND_38") (pintype "power_in"))
      (node (ref "U2") (pin "43") (pinfunction "GND_43") (pintype "power_in"))
      (node (ref "U2") (pin "44") (pinfunction "GND_44") (pintype "power_in"))
      (node (ref "U2") (pin "8") (pinfunction "GND_8") (pintype "power_in"))
      (node (ref "U2") (pin "9") (pinfunction "GND_9") (pintype "power_in"))
      (node (ref "U3") (pin "17") (pinfunction "GND_17") (pintype "power_in"))
      (node (ref "U3") (pin "18") (pinfunction "GND_18") (pintype "power_in"))
      (node (ref "U3") (pin "23") (pinfunction "GND_23") (pintype "power_in"))
      (node (ref "U3") (pin "24") (pinfunction "GND_24") (pintype "power_in"))
      (node (ref "U3") (pin "25") (pinfunction "GND_25") (pintype "power_in"))
      (node (ref "U3") (pin "26") (pinfunction "GND_26") (pintype "power_in"))
      (node (ref "U3") (pin "37") (pinfunction "GND_37") (pintype "power_in"))
      (node (ref "U3") (pin "38") (pinfunction "GND_38") (pintype "power_in"))
      (node (ref "U3") (pin "43") (pinfunction "GND_43") (pintype "power_in"))
      (node (ref "U3") (pin "44") (pinfunction "GND_44") (pintype "power_in"))
      (node (ref "U3") (pin "8") (pinfunction "GND_8") (pintype "power_in"))
      (node (ref "U3") (pin "9") (pinfunction "GND_9") (pintype "power_in"))
      (node (ref "U4") (pin "17") (pinfunction "GND_17") (pintype "power_in"))
      (node (ref "U4") (pin "18") (pinfunction "GND_18") (pintype "power_in"))
      (node (ref "U4") (pin "23") (pinfunction "GND_23") (pintype "power_in"))
      (node (ref "U4") (pin "24") (pinfunction "GND_24") (pintype "power_in"))
      (node (ref "U4") (pin "25") (pinfunction "GND_25") (pintype "power_in"))
      (node (ref "U4") (pin "26") (pinfunction "GND_26") (pintype "power_in"))
      (node (ref "U4") (pin "37") (pinfunction "GND_37") (pintype "power_in"))
      (node (ref "U4") (pin "38") (pinfunction "GND_38") (pintype "power_in"))
      (node (ref "U4") (pin "43") (pinfunction "GND_43") (pintype "power_in"))
      (node (ref "U4") (pin "44") (pinfunction "GND_44") (pintype "power_in"))
      (node (ref "U4") (pin "8") (pinfunction "GND_8") (pintype "power_in"))
      (node (ref "U4") (pin "9") (pinfunction "GND_9") (pintype "power_in"))
      (node (ref "U5") (pin "17") (pinfunction "GND_17") (pintype "power_in"))
      (node (ref "U5") (pin "18") (pinfunction "GND_18") (pintype "power_in"))
      (node (ref "U5") (pin "23") (pinfunction "GND_23") (pintype "power_in"))
      (node (ref "U5") (pin "24") (pinfunction "GND_24") (pintype "power_in"))
      (node (ref "U5") (pin "25") (pinfunction "GND_25") (pintype "power_in"))
      (node (ref "U5") (pin "26") (pinfunction "GND_26") (pintype "power_in"))
      (node (ref "U5") (pin "37") (pinfunction "GND_37") (pintype "power_in"))
      (node (ref "U5") (pin "38") (pinfunction "GND_38") (pintype "power_in"))
      (node (ref "U5") (pin "43") (pinfunction "GND_43") (pintype "power_in"))
      (node (ref "U5") (pin "44") (pinfunction "GND_44") (pintype "power_in"))
      (node (ref "U5") (pin "8") (pinfunction "GND_8") (pintype "power_in"))
      (node (ref "U5") (pin "9") (pinfunction "GND_9") (pintype "power_in"))
      (node (ref "U6") (pin "17") (pinfunction "GND_17") (pintype "power_in"))
      (node (ref "U6") (pin "18") (pinfunction "GND_18") (pintype "power_in"))
      (node (ref "U6") (pin "23") (pinfunction "GND_23") (pintype "power_in"))
      (node (ref "U6") (pin "24") (pinfunction "GND_24") (pintype "power_in"))
      (node (ref "U6") (pin "25") (pinfunction "GND_25") (pintype "power_in"))
      (node (ref "U6") (pin "26") (pinfunction "GND_26") (pintype "power_in"))
      (node (ref "U6") (pin "37") (pinfunction "GND_37") (pintype "power_in"))
      (node (ref "U6") (pin "38") (pinfunction "GND_38") (pintype "power_in"))
      (node (ref "U6") (pin "43") (pinfunction "GND_43") (pintype "power_in"))
      (node (ref "U6") (pin "44") (pinfunction "GND_44") (pintype "power_in"))
      (node (ref "U6") (pin "8") (pinfunction "GND_8") (pintype "power_in"))
      (node (ref "U6") (pin "9") (pinfunction "GND_9") (pintype "power_in"))
      (node (ref "U7") (pin "17") (pinfunction "GND_17") (pintype "power_in"))
      (node (ref "U7") (pin "18") (pinfunction "GND_18") (pintype "power_in"))
      (node (ref "U7") (pin "23") (pinfunction "GND_23") (pintype "power_in"))
      (node (ref "U7") (pin "24") (pinfunction "GND_24") (pintype "power_in"))
      (node (ref "U7") (pin "25") (pinfunction "GND_25") (pintype "power_in"))
      (node (ref "U7") (pin "26") (pinfunction "GND_26") (pintype "power_in"))
      (node (ref "U7") (pin "37") (pinfunction "GND_37") (pintype "power_in"))
      (node (ref "U7") (pin "38") (pinfunction "GND_38") (pintype "power_in"))
      (node (ref "U7") (pin "43") (pinfunction "GND_43") (pintype "power_in"))
      (node (ref "U7") (pin "44") (pinfunction "GND_44") (pintype "power_in"))
      (node (ref "U7") (pin "8") (pinfunction "GND_8") (pintype "power_in"))
      (node (ref "U7") (pin "9") (pinfunction "GND_9") (pintype "power_in"))
      (node (ref "U8") (pin "17") (pinfunction "GND_17") (pintype "power_in"))
      (node (ref "U8") (pin "18") (pinfunction "GND_18") (pintype "power_in"))
      (node (ref "U8") (pin "23") (pinfunction "GND_23") (pintype "power_in"))
      (node (ref "U8") (pin "24") (pinfunction "GND_24") (pintype "power_in"))
      (node (ref "U8") (pin "25") (pinfunction "GND_25") (pintype "power_in"))
      (node (ref "U8") (pin "26") (pinfunction "GND_26") (pintype "power_in"))
      (node (ref "U8") (pin "37") (pinfunction "GND_37") (pintype "power_in"))
      (node (ref "U8") (pin "38") (pinfunction "GND_38") (pintype "power_in"))
      (node (ref "U8") (pin "43") (pinfunction "GND_43") (pintype "power_in"))
      (node (ref "U8") (pin "44") (pinfunction "GND_44") (pintype "power_in"))
      (node (ref "U8") (pin "8") (pinfunction "GND_8") (pintype "power_in"))
      (node (ref "U8") (pin "9") (pinfunction "GND_9") (pintype "power_in"))
    )
    (net (code "134") (name "Net-(CN21-Pad149)") (class "Default")
      (node (ref "CN21") (pin "149") (pinfunction "149_149") (pintype "passive"))
      (node (ref "JS1") (pin "1") (pinfunction "1_1") (pintype "passive"))
      (node (ref "R2") (pin "2") (pinfunction "2_2") (pintype "passive"))
    )
    (net (code "135") (name "unconnected-(CN1-Pad5)") (class "Default")
      (node (ref "CN1") (pin "5") (pinfunction "5_5") (pintype "passive"))
    )
    (net (code "136") (name "unconnected-(CN2-Pad5)") (class "Default")
      (node (ref "CN2") (pin "5") (pinfunction "5_5") (pintype "passive"))
    )
    (net (code "137") (name "unconnected-(CN3-Pad5)") (class "Default")
      (node (ref "CN3") (pin "5") (pinfunction "5_5") (pintype "passive"))
    )
    (net (code "138") (name "unconnected-(CN4-Pad5)") (class "Default")
      (node (ref "CN4") (pin "5") (pinfunction "5_5") (pintype "passive"))
    )
    (net (code "139") (name "unconnected-(CN5-Pad4)") (class "Default")
      (node (ref "CN5") (pin "4") (pinfunction "4_4") (pintype "passive"))
    )
    (net (code "140") (name "unconnected-(CN6-Pad4)") (class "Default")
      (node (ref "CN6") (pin "4") (pinfunction "4_4") (pintype "passive"))
    )
    (net (code "141") (name "unconnected-(CN7-Pad4)") (class "Default")
      (node (ref "CN7") (pin "4") (pinfunction "4_4") (pintype "passive"))
    )
    (net (code "142") (name "unconnected-(CN8-Pad4)") (class "Default")
      (node (ref "CN8") (pin "4") (pinfunction "4_4") (pintype "passive"))
    )
    (net (code "143") (name "unconnected-(CN21-Pad1)") (class "Default")
      (node (ref "CN21") (pin "1") (pinfunction "1_1") (pintype "passive"))
    )
    (net (code "144") (name "unconnected-(CN21-Pad2)") (class "Default")
      (node (ref "CN21") (pin "2") (pinfunction "2_2") (pintype "passive"))
    )
    (net (code "145") (name "unconnected-(CN21-Pad3)") (class "Default")
      (node (ref "CN21") (pin "3") (pinfunction "3_3") (pintype "passive"))
    )
    (net (code "146") (name "unconnected-(CN21-Pad4)") (class "Default")
      (node (ref "CN21") (pin "4") (pinfunction "4_4") (pintype "passive"))
    )
    (net (code "147") (name "unconnected-(CN21-Pad5)") (class "Default")
      (node (ref "CN21") (pin "5") (pinfunction "5_5") (pintype "passive"))
    )
    (net (code "148") (name "unconnected-(CN21-Pad6)") (class "Default")
      (node (ref "CN21") (pin "6") (pinfunction "6_6") (pintype "passive"))
    )
    (net (code "149") (name "unconnected-(CN21-Pad7)") (class "Default")
      (node (ref "CN21") (pin "7") (pinfunction "7_7") (pintype "passive"))
    )
    (net (code "150") (name "unconnected-(CN21-Pad8)") (class "Default")
      (node (ref "CN21") (pin "8") (pinfunction "8_8") (pintype "passive"))
    )
    (net (code "151") (name "unconnected-(CN21-Pad9)") (class "Default")
      (node (ref "CN21") (pin "9") (pinfunction "9_9") (pintype "passive"))
    )
    (net (code "152") (name "unconnected-(CN21-Pad10)") (class "Default")
      (node (ref "CN21") (pin "10") (pinfunction "10_10") (pintype "passive"))
    )
    (net (code "153") (name "unconnected-(CN21-Pad11)") (class "Default")
      (node (ref "CN21") (pin "11") (pinfunction "11_11") (pintype "passive"))
    )
    (net (code "154") (name "unconnected-(CN21-Pad12)") (class "Default")
      (node (ref "CN21") (pin "12") (pinfunction "12_12") (pintype "passive"))
    )
    (net (code "155") (name "unconnected-(CN21-Pad13)") (class "Default")
      (node (ref "CN21") (pin "13") (pinfunction "13_13") (pintype "passive"))
    )
    (net (code "156") (name "unconnected-(CN21-Pad14)") (class "Default")
      (node (ref "CN21") (pin "14") (pinfunction "14_14") (pintype "passive"))
    )
    (net (code "157") (name "unconnected-(CN21-Pad15)") (class "Default")
      (node (ref "CN21") (pin "15") (pinfunction "15_15") (pintype "passive"))
    )
    (net (code "158") (name "unconnected-(CN21-Pad16)") (class "Default")
      (node (ref "CN21") (pin "16") (pinfunction "16_16") (pintype "passive"))
    )
    (net (code "159") (name "unconnected-(CN21-Pad17)") (class "Default")
      (node (ref "CN21") (pin "17") (pinfunction "17_17") (pintype "passive"))
    )
    (net (code "160") (name "unconnected-(CN21-Pad18)") (class "Default")
      (node (ref "CN21") (pin "18") (pinfunction "18_18") (pintype "passive"))
    )
    (net (code "161") (name "unconnected-(CN21-Pad19)") (class "Default")
      (node (ref "CN21") (pin "19") (pinfunction "19_19") (pintype "passive"))
    )
    (net (code "162") (name "unconnected-(CN21-Pad20)") (class "Default")
      (node (ref "CN21") (pin "20") (pinfunction "20_20") (pintype "passive"))
    )
    (net (code "163") (name "unconnected-(CN21-Pad21)") (class "Default")
      (node (ref "CN21") (pin "21") (pinfunction "21_21") (pintype "passive"))
    )
    (net (code "164") (name "unconnected-(CN21-Pad22)") (class "Default")
      (node (ref "CN21") (pin "22") (pinfunction "22_22") (pintype "passive"))
    )
    (net (code "165") (name "unconnected-(CN21-Pad23)") (class "Default")
      (node (ref "CN21") (pin "23") (pinfunction "23_23") (pintype "passive"))
    )
    (net (code "166") (name "unconnected-(CN21-Pad24)") (class "Default")
      (node (ref "CN21") (pin "24") (pinfunction "24_24") (pintype "passive"))
    )
    (net (code "167") (name "unconnected-(CN21-Pad25)") (class "Default")
      (node (ref "CN21") (pin "25") (pinfunction "25_25") (pintype "passive"))
    )
    (net (code "168") (name "unconnected-(CN21-Pad26)") (class "Default")
      (node (ref "CN21") (pin "26") (pinfunction "26_26") (pintype "passive"))
    )
    (net (code "169") (name "unconnected-(CN21-Pad27)") (class "Default")
      (node (ref "CN21") (pin "27") (pinfunction "27_27") (pintype "passive"))
    )
    (net (code "170") (name "unconnected-(CN21-Pad28)") (class "Default")
      (node (ref "CN21") (pin "28") (pinfunction "28_28") (pintype "passive"))
    )
    (net (code "171") (name "unconnected-(CN21-Pad29)") (class "Default")
      (node (ref "CN21") (pin "29") (pinfunction "29_29") (pintype "passive"))
    )
    (net (code "172") (name "unconnected-(CN21-Pad30)") (class "Default")
      (node (ref "CN21") (pin "30") (pinfunction "30_30") (pintype "passive"))
    )
    (net (code "173") (name "unconnected-(CN21-Pad31)") (class "Default")
      (node (ref "CN21") (pin "31") (pinfunction "31_31") (pintype "passive"))
    )
    (net (code "174") (name "unconnected-(CN21-Pad32)") (class "Default")
      (node (ref "CN21") (pin "32") (pinfunction "32_32") (pintype "passive"))
    )
    (net (code "175") (name "unconnected-(CN21-Pad33)") (class "Default")
      (node (ref "CN21") (pin "33") (pinfunction "33_33") (pintype "passive"))
    )
    (net (code "176") (name "unconnected-(CN21-Pad34)") (class "Default")
      (node (ref "CN21") (pin "34") (pinfunction "34_34") (pintype "passive"))
    )
    (net (code "177") (name "unconnected-(CN21-Pad35)") (class "Default")
      (node (ref "CN21") (pin "35") (pinfunction "35_35") (pintype "passive"))
    )
    (net (code "178") (name "unconnected-(CN21-Pad36)") (class "Default")
      (node (ref "CN21") (pin "36") (pinfunction "36_36") (pintype "passive"))
    )
    (net (code "179") (name "unconnected-(CN21-Pad37)") (class "Default")
      (node (ref "CN21") (pin "37") (pinfunction "37_37") (pintype "passive"))
    )
    (net (code "180") (name "unconnected-(CN21-Pad38)") (class "Default")
      (node (ref "CN21") (pin "38") (pinfunction "38_38") (pintype "passive"))
    )
    (net (code "181") (name "unconnected-(CN21-Pad39)") (class "Default")
      (node (ref "CN21") (pin "39") (pinfunction "39_39") (pintype "passive"))
    )
    (net (code "182") (name "unconnected-(CN21-Pad40)") (class "Default")
      (node (ref "CN21") (pin "40") (pinfunction "40_40") (pintype "passive"))
    )
    (net (code "183") (name "unconnected-(CN21-Pad41)") (class "Default")
      (node (ref "CN21") (pin "41") (pinfunction "41_41") (pintype "passive"))
    )
    (net (code "184") (name "unconnected-(CN21-Pad42)") (class "Default")
      (node (ref "CN21") (pin "42") (pinfunction "42_42") (pintype "passive"))
    )
    (net (code "185") (name "unconnected-(CN21-Pad43)") (class "Default")
      (node (ref "CN21") (pin "43") (pinfunction "43_43") (pintype "passive"))
    )
    (net (code "186") (name "unconnected-(CN21-Pad44)") (class "Default")
      (node (ref "CN21") (pin "44") (pinfunction "44_44") (pintype "passive"))
    )
    (net (code "187") (name "unconnected-(CN21-Pad46)") (class "Default")
      (node (ref "CN21") (pin "46") (pinfunction "46_46") (pintype "passive"))
    )
    (net (code "188") (name "unconnected-(CN21-Pad52)") (class "Default")
      (node (ref "CN21") (pin "52") (pinfunction "52_52") (pintype "passive"))
    )
    (net (code "189") (name "unconnected-(CN21-Pad58)") (class "Default")
      (node (ref "CN21") (pin "58") (pinfunction "58_58") (pintype "passive"))
    )
    (net (code "190") (name "unconnected-(CN21-Pad64)") (class "Default")
      (node (ref "CN21") (pin "64") (pinfunction "64_64") (pintype "passive"))
    )
    (net (code "191") (name "unconnected-(CN21-Pad70)") (class "Default")
      (node (ref "CN21") (pin "70") (pinfunction "70_70") (pintype "passive"))
    )
    (net (code "192") (name "unconnected-(CN21-Pad76)") (class "Default")
      (node (ref "CN21") (pin "76") (pinfunction "76_76") (pintype "passive"))
    )
    (net (code "193") (name "unconnected-(CN21-Pad82)") (class "Default")
      (node (ref "CN21") (pin "82") (pinfunction "82_82") (pintype "passive"))
    )
    (net (code "194") (name "unconnected-(CN21-Pad88)") (class "Default")
      (node (ref "CN21") (pin "88") (pinfunction "88_88") (pintype "passive"))
    )
    (net (code "195") (name "unconnected-(CN21-Pad94)") (class "Default")
      (node (ref "CN21") (pin "94") (pinfunction "94_94") (pintype "passive"))
    )
    (net (code "196") (name "unconnected-(CN21-Pad95)") (class "Default")
      (node (ref "CN21") (pin "95") (pinfunction "95_95") (pintype "passive"))
    )
    (net (code "197") (name "unconnected-(CN21-Pad96)") (class "Default")
      (node (ref "CN21") (pin "96") (pinfunction "96_96") (pintype "passive"))
    )
    (net (code "198") (name "unconnected-(CN21-Pad97)") (class "Default")
      (node (ref "CN21") (pin "97") (pinfunction "97_97") (pintype "passive"))
    )
    (net (code "199") (name "unconnected-(CN21-Pad98)") (class "Default")
      (node (ref "CN21") (pin "98") (pinfunction "98_98") (pintype "passive"))
    )
    (net (code "200") (name "unconnected-(CN21-Pad100)") (class "Default")
      (node (ref "CN21") (pin "100") (pinfunction "100_100") (pintype "passive"))
    )
    (net (code "201") (name "unconnected-(CN21-Pad106)") (class "Default")
      (node (ref "CN21") (pin "106") (pinfunction "106_106") (pintype "passive"))
    )
    (net (code "202") (name "unconnected-(CN21-Pad112)") (class "Default")
      (node (ref "CN21") (pin "112") (pinfunction "112_112") (pintype "passive"))
    )
    (net (code "203") (name "unconnected-(CN21-Pad118)") (class "Default")
      (node (ref "CN21") (pin "118") (pinfunction "118_118") (pintype "passive"))
    )
    (net (code "204") (name "unconnected-(CN21-Pad124)") (class "Default")
      (node (ref "CN21") (pin "124") (pinfunction "124_124") (pintype "passive"))
    )
    (net (code "205") (name "unconnected-(CN21-Pad130)") (class "Default")
      (node (ref "CN21") (pin "130") (pinfunction "130_130") (pintype "passive"))
    )
    (net (code "206") (name "unconnected-(CN21-Pad136)") (class "Default")
      (node (ref "CN21") (pin "136") (pinfunction "136_136") (pintype "passive"))
    )
    (net (code "207") (name "unconnected-(CN21-Pad142)") (class "Default")
      (node (ref "CN21") (pin "142") (pinfunction "142_142") (pintype "passive"))
    )
    (net (code "208") (name "unconnected-(CN21-Pad148)") (class "Default")
      (node (ref "CN21") (pin "148") (pinfunction "148_148") (pintype "passive"))
    )
    (net (code "209") (name "unconnected-(CN21-Pad150)") (class "Default")
      (node (ref "CN21") (pin "150") (pinfunction "150_150") (pintype "passive"))
    )
    (net (code "210") (name "unconnected-(CN21-Pad154)") (class "Default")
      (node (ref "CN21") (pin "154") (pinfunction "154_154") (pintype "passive"))
    )
    (net (code "211") (name "unconnected-(CN21-Pad155)") (class "Default")
      (node (ref "CN21") (pin "155") (pinfunction "155_155") (pintype "passive"))
    )
    (net (code "212") (name "unconnected-(CN21-Pad156)") (class "Default")
      (node (ref "CN21") (pin "156") (pinfunction "156_156") (pintype "passive"))
    )
    (net (code "213") (name "unconnected-(CN21-Pad157)") (class "Default")
      (node (ref "CN21") (pin "157") (pinfunction "157_157") (pintype "passive"))
    )
    (net (code "214") (name "unconnected-(CN21-Pad158)") (class "Default")
      (node (ref "CN21") (pin "158") (pinfunction "158_158") (pintype "passive"))
    )
    (net (code "215") (name "unconnected-(U1B-NC-Pad6)") (class "Default")
      (node (ref "U1") (pin "6") (pinfunction "NC_6") (pintype "passive"))
    )
    (net (code "216") (name "unconnected-(U1B-NC-Pad30)") (class "Default")
      (node (ref "U1") (pin "30") (pinfunction "NC_30") (pintype "passive"))
    )
    (net (code "217") (name "unconnected-(U1B-NC-Pad31)") (class "Default")
      (node (ref "U1") (pin "31") (pinfunction "NC_31") (pintype "passive"))
    )
    (net (code "218") (name "unconnected-(U1B-NC-Pad35)") (class "Default")
      (node (ref "U1") (pin "35") (pinfunction "NC_35") (pintype "passive"))
    )
    (net (code "219") (name "unconnected-(U1B-NC-Pad36)") (class "Default")
      (node (ref "U1") (pin "36") (pinfunction "NC_36") (pintype "passive"))
    )
    (net (code "220") (name "unconnected-(U2B-NC-Pad6)") (class "Default")
      (node (ref "U2") (pin "6") (pinfunction "NC_6") (pintype "passive"))
    )
    (net (code "221") (name "unconnected-(U2B-NC-Pad30)") (class "Default")
      (node (ref "U2") (pin "30") (pinfunction "NC_30") (pintype "passive"))
    )
    (net (code "222") (name "unconnected-(U2B-NC-Pad31)") (class "Default")
      (node (ref "U2") (pin "31") (pinfunction "NC_31") (pintype "passive"))
    )
    (net (code "223") (name "unconnected-(U2B-NC-Pad35)") (class "Default")
      (node (ref "U2") (pin "35") (pinfunction "NC_35") (pintype "passive"))
    )
    (net (code "224") (name "unconnected-(U2B-NC-Pad36)") (class "Default")
      (node (ref "U2") (pin "36") (pinfunction "NC_36") (pintype "passive"))
    )
    (net (code "225") (name "unconnected-(U3B-NC-Pad6)") (class "Default")
      (node (ref "U3") (pin "6") (pinfunction "NC_6") (pintype "passive"))
    )
    (net (code "226") (name "unconnected-(U3B-NC-Pad30)") (class "Default")
      (node (ref "U3") (pin "30") (pinfunction "NC_30") (pintype "passive"))
    )
    (net (code "227") (name "unconnected-(U3B-NC-Pad31)") (class "Default")
      (node (ref "U3") (pin "31") (pinfunction "NC_31") (pintype "passive"))
    )
    (net (code "228") (name "unconnected-(U3B-NC-Pad35)") (class "Default")
      (node (ref "U3") (pin "35") (pinfunction "NC_35") (pintype "passive"))
    )
    (net (code "229") (name "unconnected-(U3B-NC-Pad36)") (class "Default")
      (node (ref "U3") (pin "36") (pinfunction "NC_36") (pintype "passive"))
    )
    (net (code "230") (name "unconnected-(U4B-NC-Pad6)") (class "Default")
      (node (ref "U4") (pin "6") (pinfunction "NC_6") (pintype "passive"))
    )
    (net (code "231") (name "unconnected-(U4B-NC-Pad30)") (class "Default")
      (node (ref "U4") (pin "30") (pinfunction "NC_30") (pintype "passive"))
    )
    (net (code "232") (name "unconnected-(U4B-NC-Pad31)") (class "Default")
      (node (ref "U4") (pin "31") (pinfunction "NC_31") (pintype "passive"))
    )
    (net (code "233") (name "unconnected-(U4B-NC-Pad35)") (class "Default")
      (node (ref "U4") (pin "35") (pinfunction "NC_35") (pintype "passive"))
    )
    (net (code "234") (name "unconnected-(U4B-NC-Pad36)") (class "Default")
      (node (ref "U4") (pin "36") (pinfunction "NC_36") (pintype "passive"))
    )
    (net (code "235") (name "unconnected-(U5B-NC-Pad6)") (class "Default")
      (node (ref "U5") (pin "6") (pinfunction "NC_6") (pintype "passive"))
    )
    (net (code "236") (name "unconnected-(U5B-NC-Pad30)") (class "Default")
      (node (ref "U5") (pin "30") (pinfunction "NC_30") (pintype "passive"))
    )
    (net (code "237") (name "unconnected-(U5B-NC-Pad31)") (class "Default")
      (node (ref "U5") (pin "31") (pinfunction "NC_31") (pintype "passive"))
    )
    (net (code "238") (name "unconnected-(U5B-NC-Pad35)") (class "Default")
      (node (ref "U5") (pin "35") (pinfunction "NC_35") (pintype "passive"))
    )
    (net (code "239") (name "unconnected-(U5B-NC-Pad36)") (class "Default")
      (node (ref "U5") (pin "36") (pinfunction "NC_36") (pintype "passive"))
    )
    (net (code "240") (name "unconnected-(U6B-NC-Pad6)") (class "Default")
      (node (ref "U6") (pin "6") (pinfunction "NC_6") (pintype "passive"))
    )
    (net (code "241") (name "unconnected-(U6B-NC-Pad30)") (class "Default")
      (node (ref "U6") (pin "30") (pinfunction "NC_30") (pintype "passive"))
    )
    (net (code "242") (name "unconnected-(U6B-NC-Pad31)") (class "Default")
      (node (ref "U6") (pin "31") (pinfunction "NC_31") (pintype "passive"))
    )
    (net (code "243") (name "unconnected-(U6B-NC-Pad35)") (class "Default")
      (node (ref "U6") (pin "35") (pinfunction "NC_35") (pintype "passive"))
    )
    (net (code "244") (name "unconnected-(U6B-NC-Pad36)") (class "Default")
      (node (ref "U6") (pin "36") (pinfunction "NC_36") (pintype "passive"))
    )
    (net (code "245") (name "unconnected-(U7B-NC-Pad6)") (class "Default")
      (node (ref "U7") (pin "6") (pinfunction "NC_6") (pintype "passive"))
    )
    (net (code "246") (name "unconnected-(U7B-NC-Pad30)") (class "Default")
      (node (ref "U7") (pin "30") (pinfunction "NC_30") (pintype "passive"))
    )
    (net (code "247") (name "unconnected-(U7B-NC-Pad31)") (class "Default")
      (node (ref "U7") (pin "31") (pinfunction "NC_31") (pintype "passive"))
    )
    (net (code "248") (name "unconnected-(U7B-NC-Pad35)") (class "Default")
      (node (ref "U7") (pin "35") (pinfunction "NC_35") (pintype "passive"))
    )
    (net (code "249") (name "unconnected-(U7B-NC-Pad36)") (class "Default")
      (node (ref "U7") (pin "36") (pinfunction "NC_36") (pintype "passive"))
    )
    (net (code "250") (name "unconnected-(U8B-NC-Pad6)") (class "Default")
      (node (ref "U8") (pin "6") (pinfunction "NC_6") (pintype "passive"))
    )
    (net (code "251") (name "unconnected-(U8B-NC-Pad30)") (class "Default")
      (node (ref "U8") (pin "30") (pinfunction "NC_30") (pintype "passive"))
    )
    (net (code "252") (name "unconnected-(U8B-NC-Pad31)") (class "Default")
      (node (ref "U8") (pin "31") (pinfunction "NC_31") (pintype "passive"))
    )
    (net (code "253") (name "unconnected-(U8B-NC-Pad35)") (class "Default")
      (node (ref "U8") (pin "35") (pinfunction "NC_35") (pintype "passive"))
    )
    (net (code "254") (name "unconnected-(U8B-NC-Pad36)") (class "Default")
      (node (ref "U8") (pin "36") (pinfunction "NC_36") (pintype "passive"))
    )
  )
)
